# Loongson_Drivers.net
KiCad netlist of a schematic drawn in EasyEDA Pro
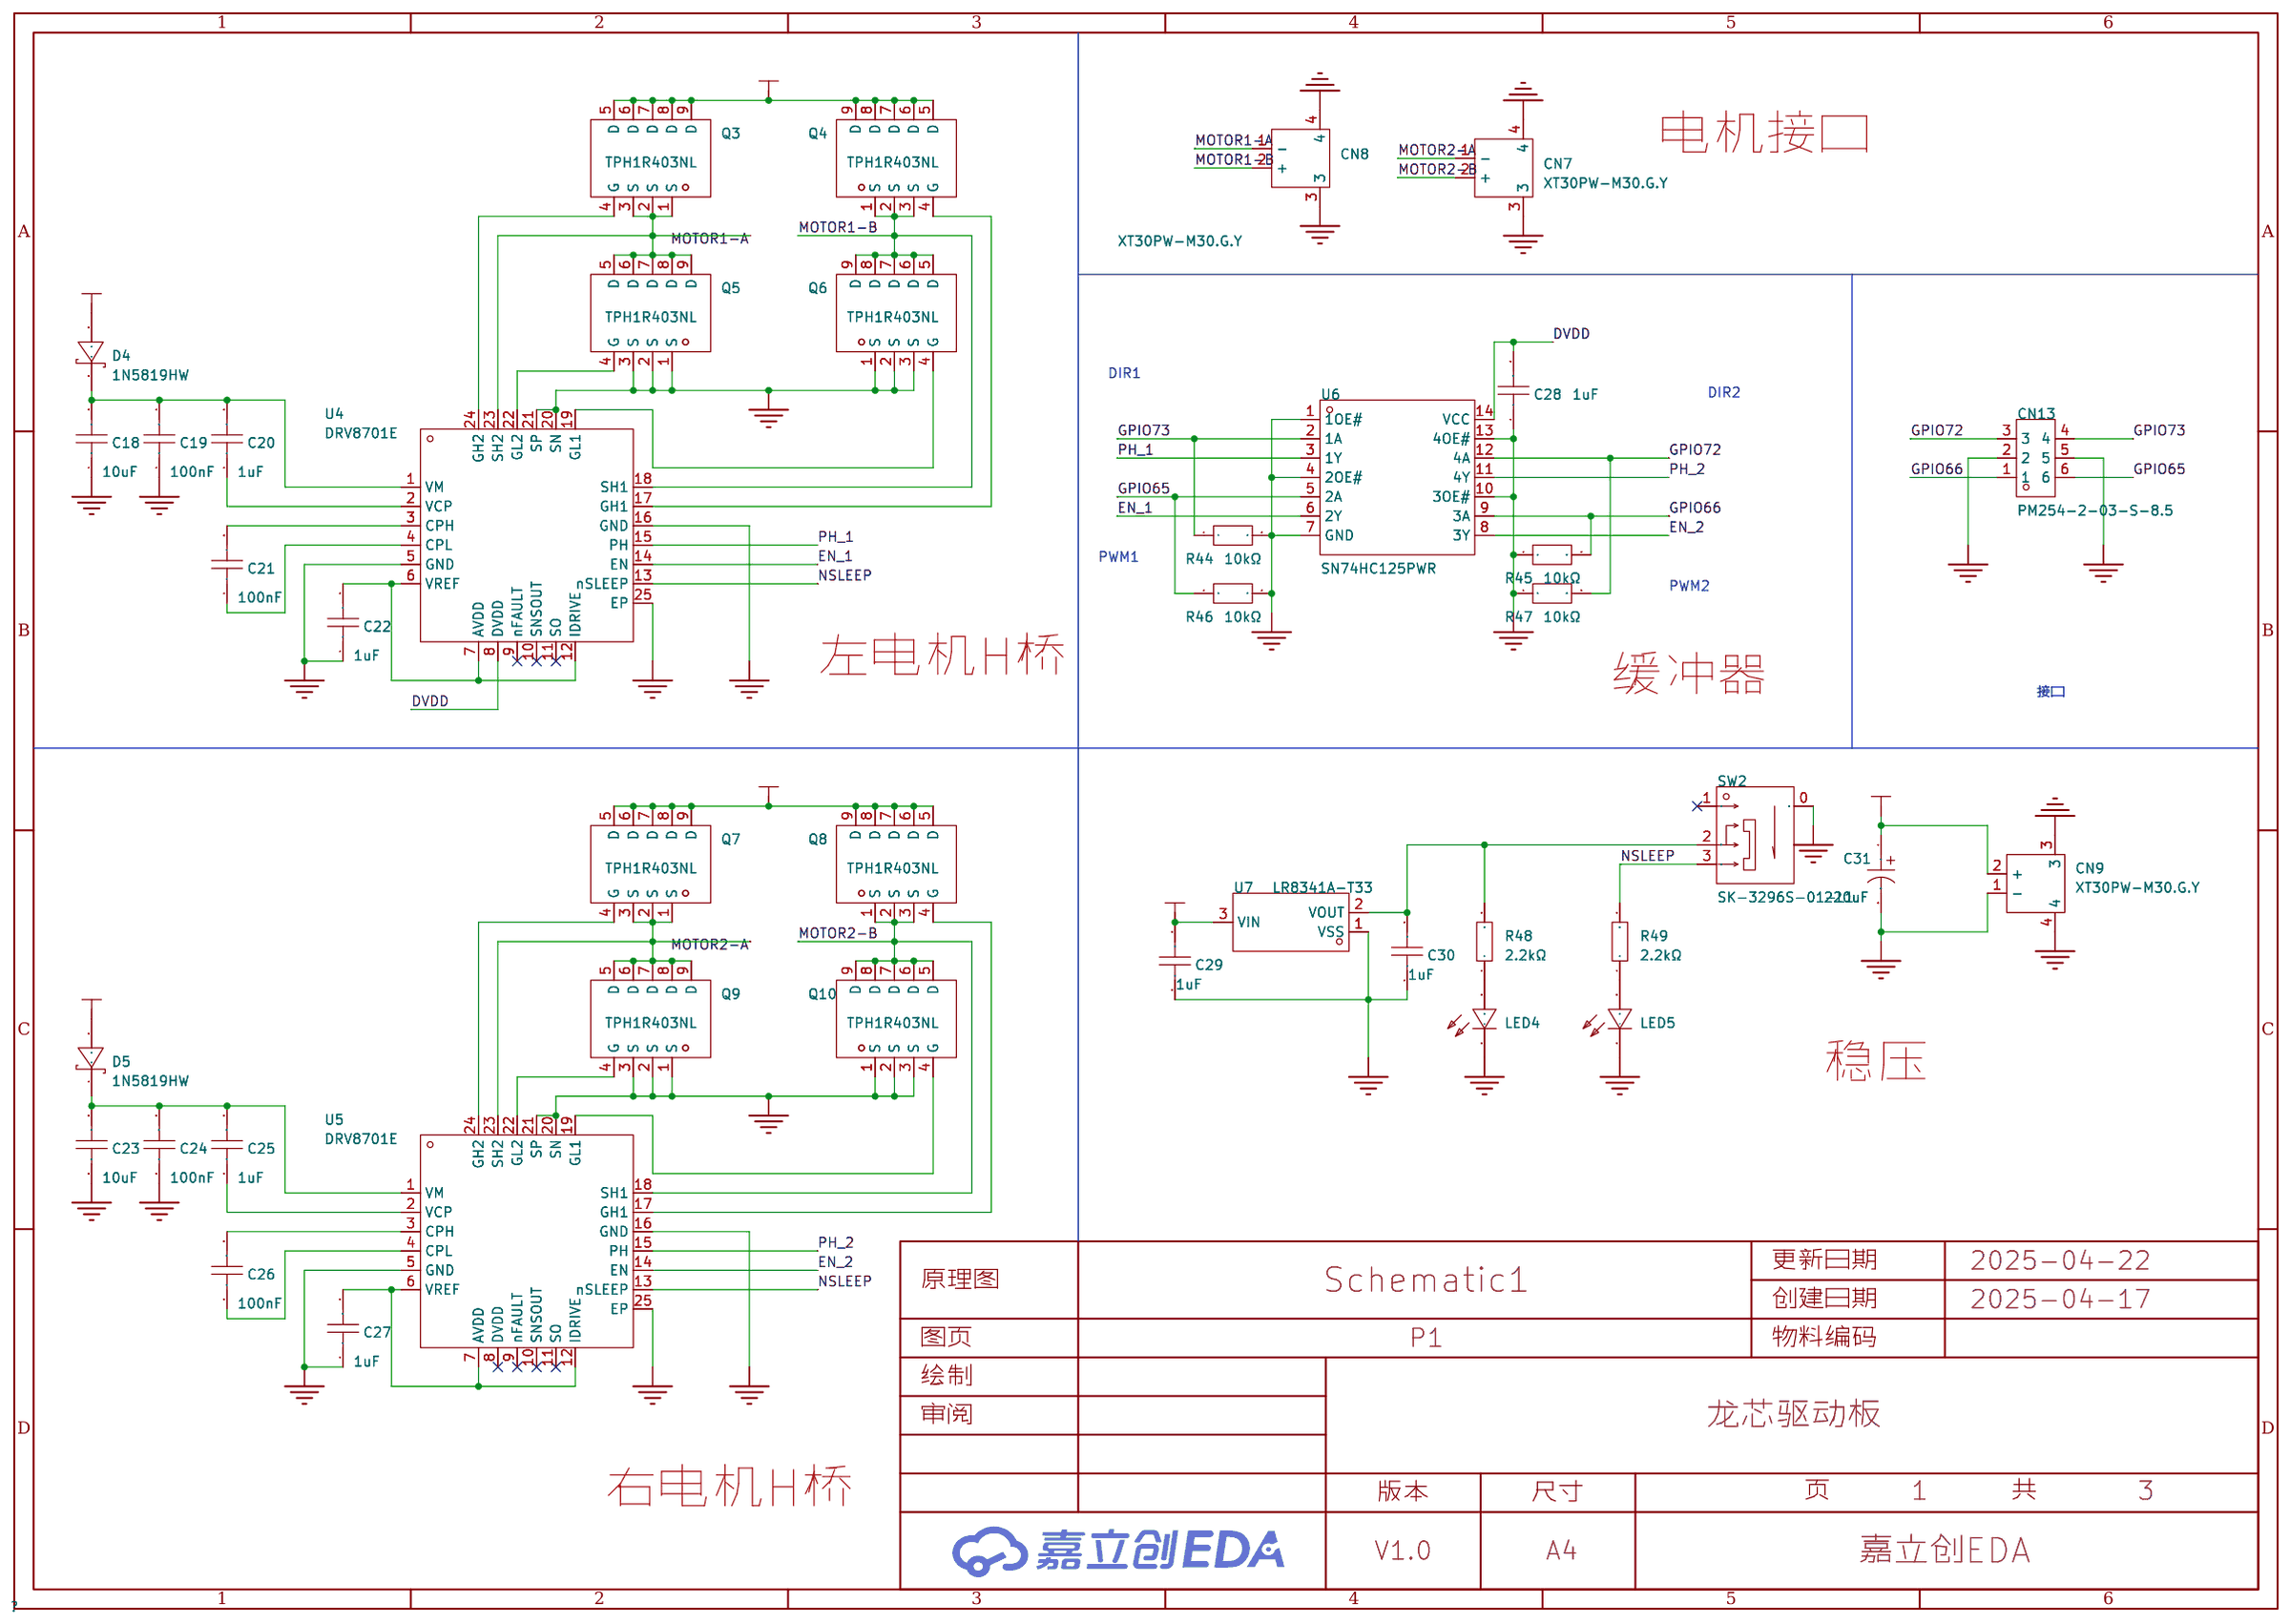
[diagram p0: P1]
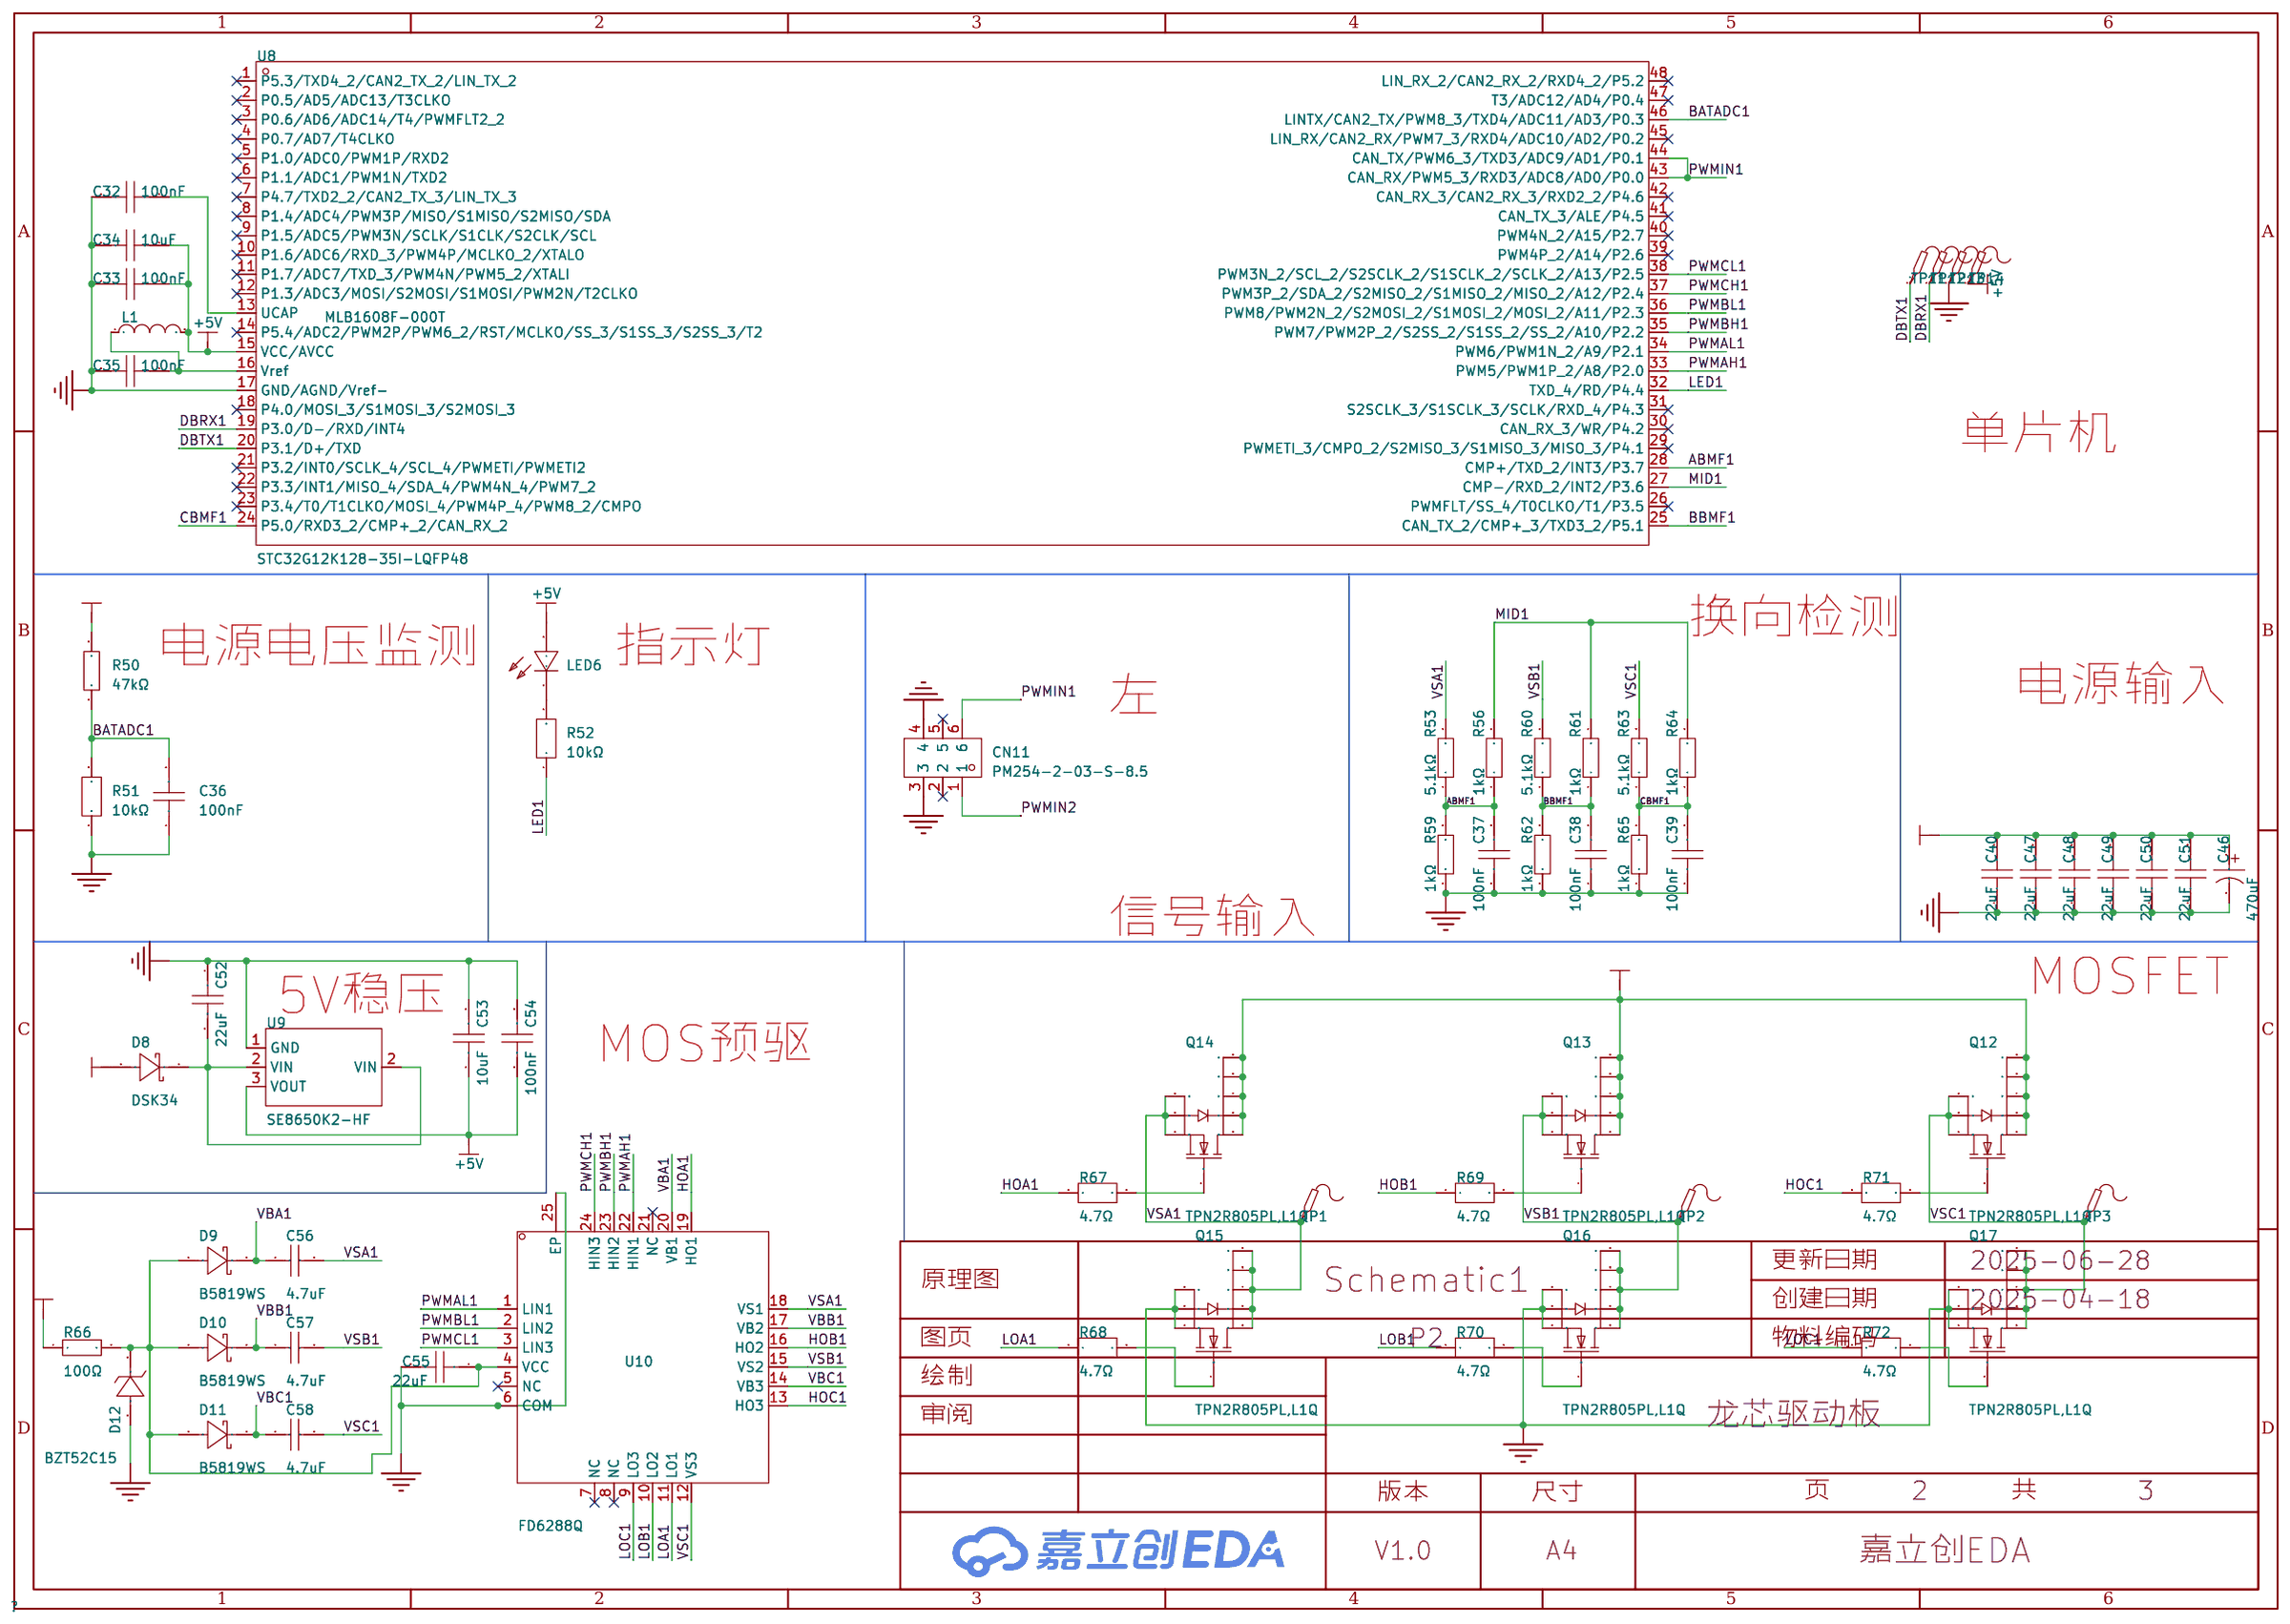
[diagram p1: P2]
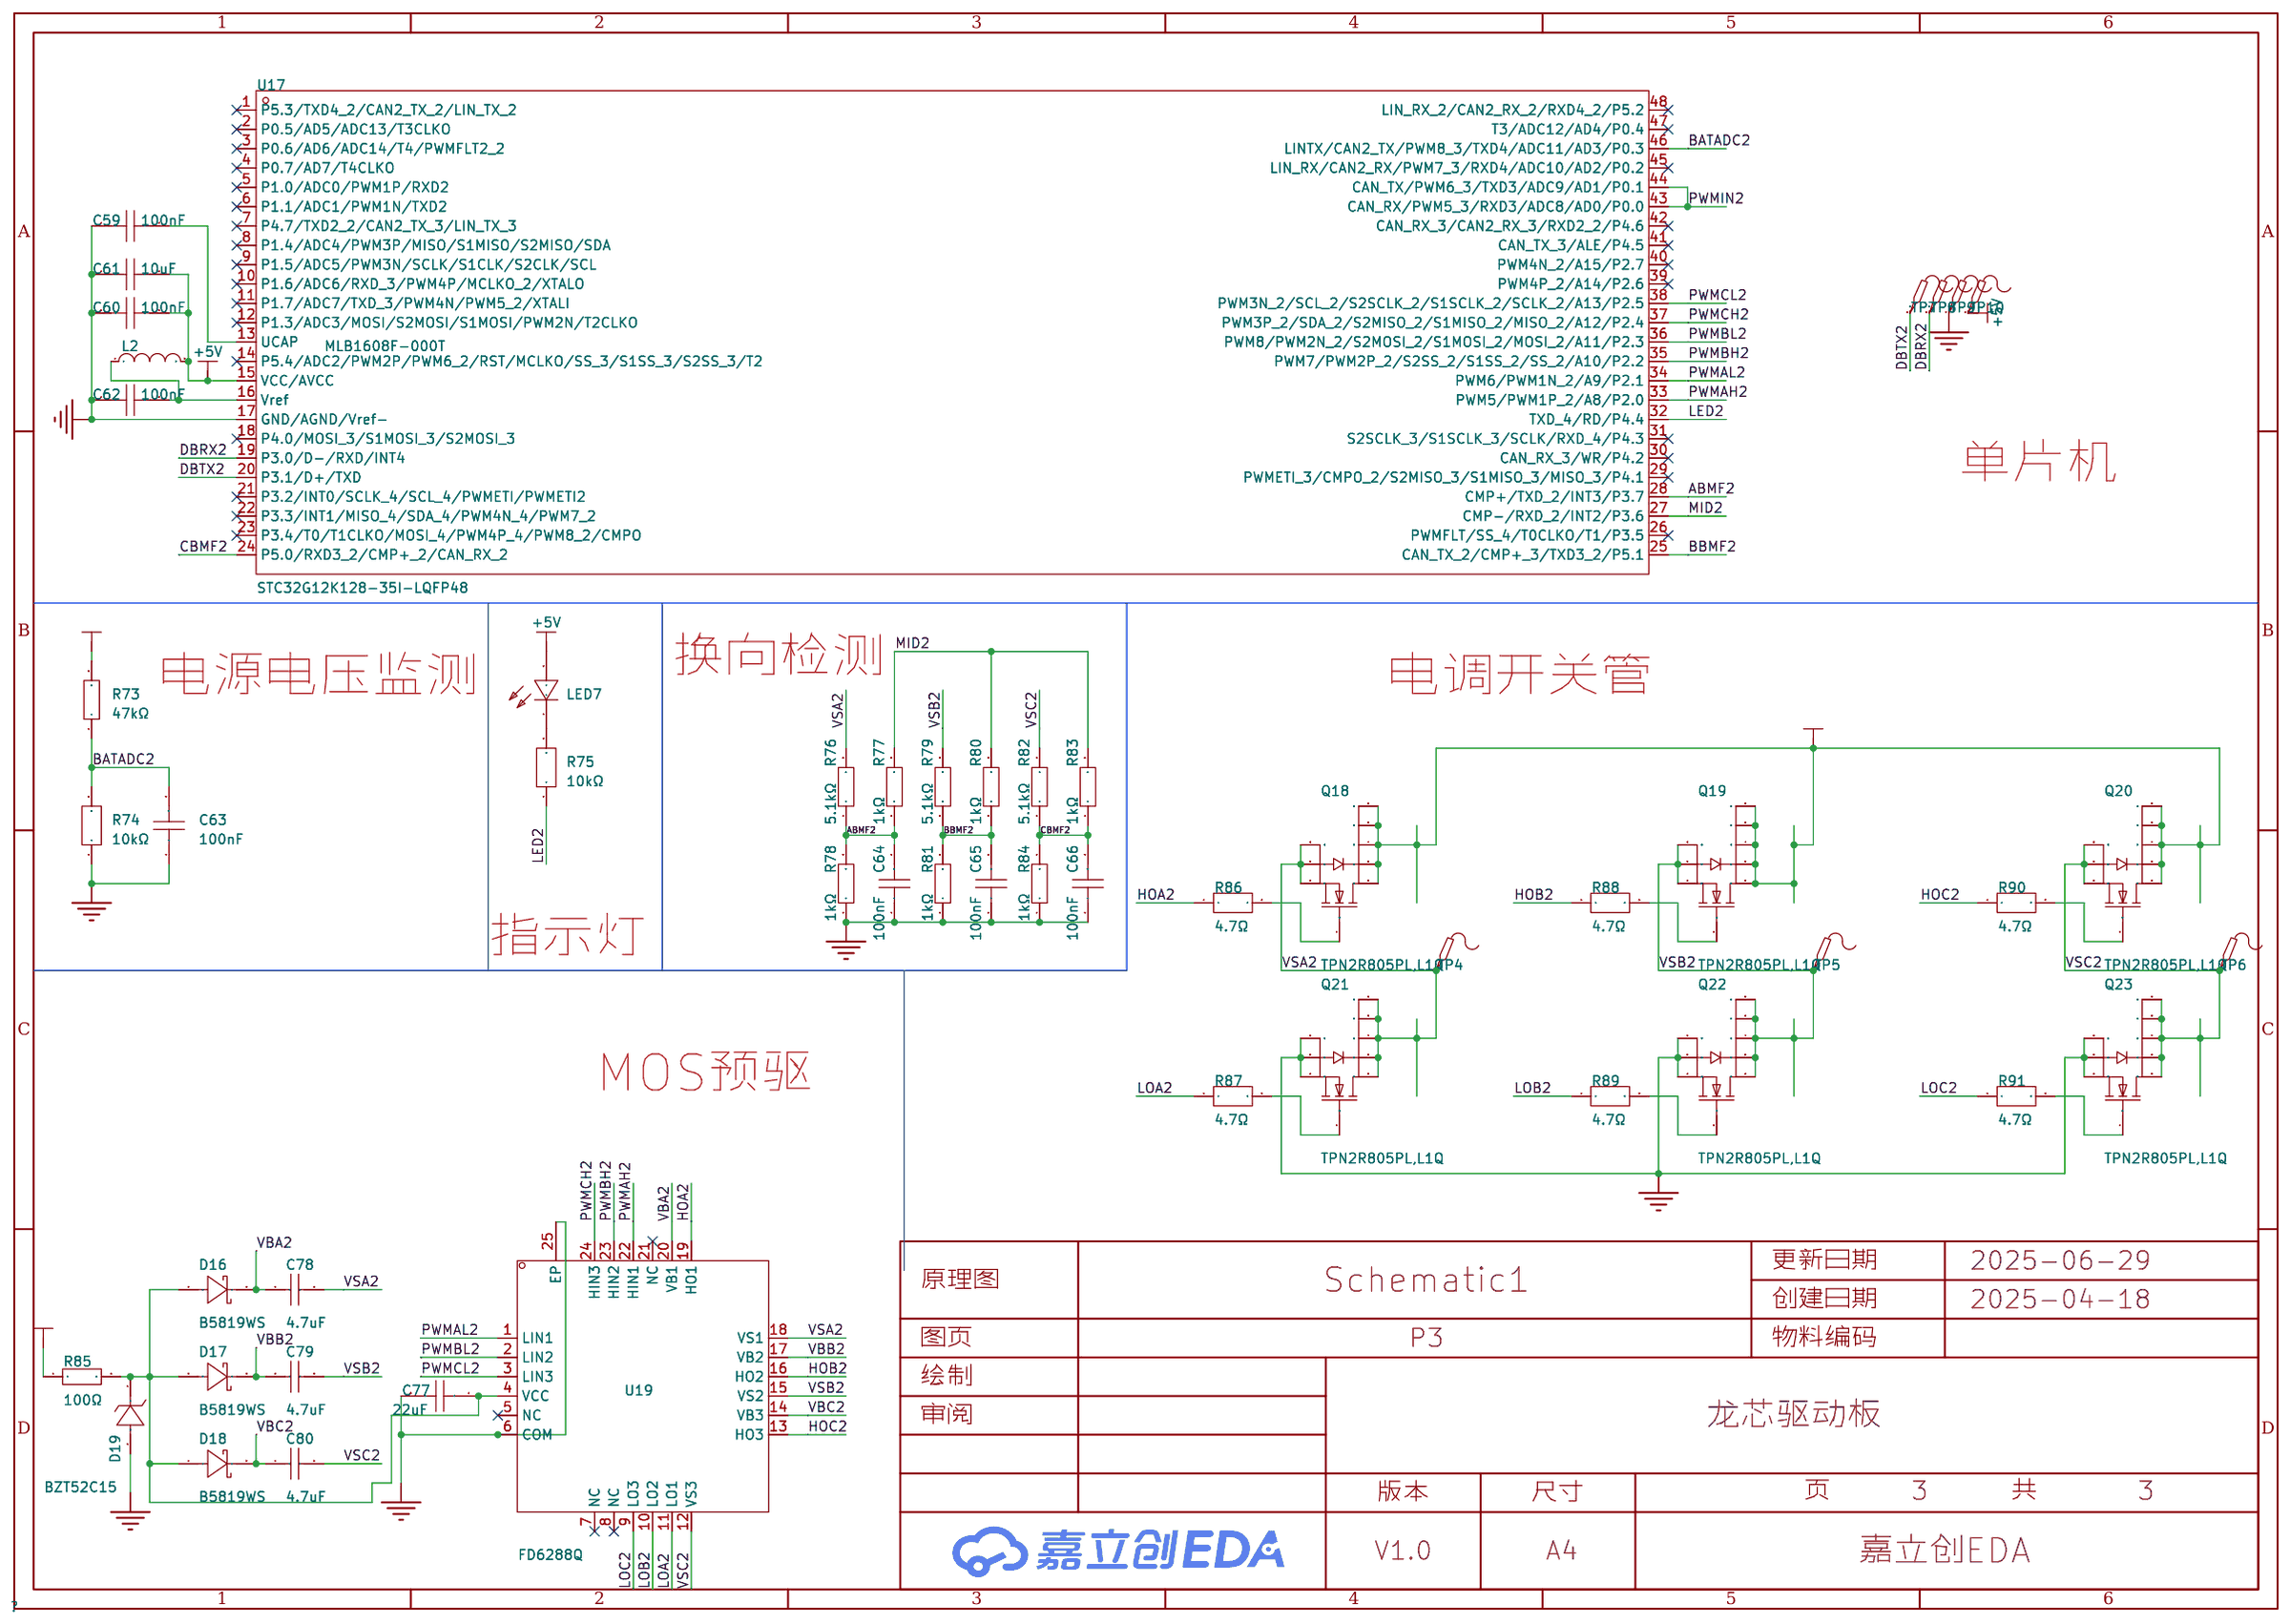
[diagram p2: P3]

(export (version "E")
  (design (tool "Eeschema 10.0.6"))
  (components
    (comp (ref "C18")
      (value "10uF")
      (footprint "easyedapro:C0805")
      (description "容值:10uF;精度:±10%;额定电压:35V;材质(温度系数):X5R;")
      (fields
        (field (name "Manufacturer Part") "CGA0805X5R106K350MT")
        (field (name "Manufacturer") "HRE(芯声)")
      )
      (libsource (lib "easyedapro") (part "CGA0805X5R106K350MT"))
    )
    (comp (ref "C19")
      (value "100nF")
      (footprint "easyedapro:C0603")
      (description "容值:100nF;精度:±10%;额定电压:35V;材质(温度系数):X7R;")
      (fields
        (field (name "Manufacturer Part") "GMK107B7104KAHT")
        (field (name "Manufacturer") "TAIYO YUDEN(太诱)")
      )
      (libsource (lib "easyedapro") (part "GMK107B7104KAHT"))
    )
    (comp (ref "C20")
      (value "1uF")
      (footprint "easyedapro:C0603")
      (description "容值:1uF;精度:±10%;额定电压:50V;材质(温度系数):X5R;")
      (fields
        (field (name "Manufacturer Part") "CL10A105KB8NNNC")
        (field (name "Manufacturer") "SAMSUNG(三星)")
      )
      (libsource (lib "easyedapro") (part "CL10A105KB8NNNC"))
    )
    (comp (ref "C21")
      (value "100nF")
      (footprint "easyedapro:C0603")
      (description "容值:100nF;精度:±10%;额定电压:35V;材质(温度系数):X7R;")
      (fields
        (field (name "Manufacturer Part") "GMK107B7104KAHT")
        (field (name "Manufacturer") "TAIYO YUDEN(太诱)")
      )
      (libsource (lib "easyedapro") (part "GMK107B7104KAHT"))
    )
    (comp (ref "C22")
      (value "1uF")
      (footprint "easyedapro:C0603")
      (description "容值:1uF;精度:±10%;额定电压:50V;材质(温度系数):X5R;")
      (fields
        (field (name "Manufacturer Part") "CL10A105KB8NNNC")
        (field (name "Manufacturer") "SAMSUNG(三星)")
      )
      (libsource (lib "easyedapro") (part "CL10A105KB8NNNC"))
    )
    (comp (ref "C23")
      (value "10uF")
      (footprint "easyedapro:C0805")
      (description "容值:10uF;精度:±10%;额定电压:35V;材质(温度系数):X5R;")
      (fields
        (field (name "Manufacturer Part") "CGA0805X5R106K350MT")
        (field (name "Manufacturer") "HRE(芯声)")
      )
      (libsource (lib "easyedapro") (part "CGA0805X5R106K350MT"))
    )
    (comp (ref "C24")
      (value "100nF")
      (footprint "easyedapro:C0603")
      (description "容值:100nF;精度:±10%;额定电压:35V;材质(温度系数):X7R;")
      (fields
        (field (name "Manufacturer Part") "GMK107B7104KAHT")
        (field (name "Manufacturer") "TAIYO YUDEN(太诱)")
      )
      (libsource (lib "easyedapro") (part "GMK107B7104KAHT"))
    )
    (comp (ref "C25")
      (value "1uF")
      (footprint "easyedapro:C0603")
      (description "容值:1uF;精度:±10%;额定电压:50V;材质(温度系数):X5R;")
      (fields
        (field (name "Manufacturer Part") "CL10A105KB8NNNC")
        (field (name "Manufacturer") "SAMSUNG(三星)")
      )
      (libsource (lib "easyedapro") (part "CL10A105KB8NNNC"))
    )
    (comp (ref "C26")
      (value "100nF")
      (footprint "easyedapro:C0603")
      (description "容值:100nF;精度:±10%;额定电压:35V;材质(温度系数):X7R;")
      (fields
        (field (name "Manufacturer Part") "GMK107B7104KAHT")
        (field (name "Manufacturer") "TAIYO YUDEN(太诱)")
      )
      (libsource (lib "easyedapro") (part "GMK107B7104KAHT"))
    )
    (comp (ref "C27")
      (value "1uF")
      (footprint "easyedapro:C0603")
      (description "容值:1uF;精度:±10%;额定电压:50V;材质(温度系数):X5R;")
      (fields
        (field (name "Manufacturer Part") "CL10A105KB8NNNC")
        (field (name "Manufacturer") "SAMSUNG(三星)")
      )
      (libsource (lib "easyedapro") (part "CL10A105KB8NNNC"))
    )
    (comp (ref "C28")
      (value "1uF")
      (footprint "easyedapro:C0603")
      (description "容值:1uF;精度:±10%;额定电压:50V;材质(温度系数):X5R;")
      (fields
        (field (name "Manufacturer Part") "CL10A105KB8NNNC")
        (field (name "Manufacturer") "SAMSUNG(三星)")
      )
      (libsource (lib "easyedapro") (part "CL10A105KB8NNNC"))
    )
    (comp (ref "C29")
      (value "1uF")
      (footprint "easyedapro:C0603")
      (description "容值:1uF;精度:±10%;额定电压:50V;材质(温度系数):X5R;")
      (fields
        (field (name "Manufacturer Part") "CL10A105KB8NNNC")
        (field (name "Manufacturer") "SAMSUNG(三星)")
      )
      (libsource (lib "easyedapro") (part "CL10A105KB8NNNC"))
    )
    (comp (ref "C30")
      (value "1uF")
      (footprint "easyedapro:C0603")
      (description "容值:1uF;精度:±10%;额定电压:50V;材质(温度系数):X5R;")
      (fields
        (field (name "Manufacturer Part") "CL10A105KB8NNNC")
        (field (name "Manufacturer") "SAMSUNG(三星)")
      )
      (libsource (lib "easyedapro") (part "CL10A105KB8NNNC"))
    )
    (comp (ref "C31")
      (value "220uF")
      (footprint "easyedapro:CAP-SMD_BD8.0-L8.3-W8.3-LS9.1-FD")
      (description "容值:220uF;精度:±20%;额定电压:35V;")
      (fields (field (name "Manufacturer Part") "HV1V227M0810PZ") (field (name "Manufacturer") "HONOR(荣誉)"))
      (libsource (lib "easyedapro") (part "HV1V227M0810PZ"))
    )
    (comp (ref "CN7")
      (value "XT30PW-M30.G.Y")
      (footprint "easyedapro:CONN-TH_XT30PW-M")
      (description "类别:-;类型1:-;")
      (fields (field (name "Manufacturer") "AMASS(艾迈斯)"))
      (libsource (lib "easyedapro") (part "XT30PW-M"))
    )
    (comp (ref "CN8")
      (value "XT30PW-M30.G.Y")
      (footprint "easyedapro:CONN-TH_XT30PW-M")
      (description "类别:-;类型1:-;")
      (fields (field (name "Manufacturer") "AMASS(艾迈斯)"))
      (libsource (lib "easyedapro") (part "XT30PW-M"))
    )
    (comp (ref "CN9")
      (value "XT30PW-M30.G.Y")
      (footprint "easyedapro:CONN-TH_XT30PW-M")
      (description "类别:-;类型1:-;")
      (fields (field (name "Manufacturer") "AMASS(艾迈斯)"))
      (libsource (lib "easyedapro") (part "XT30PW-M"))
    )
    (comp (ref "CN13")
      (value "PM254-2-03-S-8.5")
      (footprint "easyedapro:HDR-SMD_6P-P2.54-V-F-R2-C3-LS7.0")
      (fields (field (name "Manufacturer") "HCTL(华灿天禄)"))
      (libsource (lib "easyedapro") (part "PM254-2-03-S-8.5"))
    )
    (comp (ref "D4")
      (value "1N5819HW")
      (footprint "easyedapro:SOD-123_L2.7-W1.6-LS3.7-RD")
      (description "正向压降(Vf):450mV@1A;直流反向耐压(Vr):40V;整流电流:1A;")
      (fields (field (name "Manufacturer") "DIODES(美台)"))
      (libsource (lib "easyedapro") (part "1N5819HW-7-F"))
    )
    (comp (ref "D5")
      (value "1N5819HW")
      (footprint "easyedapro:SOD-123_L2.7-W1.6-LS3.7-RD")
      (description "正向压降(Vf):450mV@1A;直流反向耐压(Vr):40V;整流电流:1A;")
      (fields (field (name "Manufacturer") "DIODES(美台)"))
      (libsource (lib "easyedapro") (part "1N5819HW-7-F"))
    )
    (comp (ref "LED4")
      (value "NCD0603R1")
      (footprint "easyedapro:LED0603-RD_RED")
      (fields (field (name "Manufacturer") "国星光电"))
      (libsource (lib "easyedapro") (part "FC-DA1608HRK-620D"))
    )
    (comp (ref "LED5")
      (value "NCD0603B1")
      (footprint "easyedapro:LED0603-RD")
      (fields (field (name "Manufacturer") "国星光电"))
      (libsource (lib "easyedapro") (part "FC-DA1608BK-470H10"))
    )
    (comp (ref "Q3")
      (value "TPH1R403NL")
      (footprint "easyedapro:DSOP-8_L5.0-W5.0-P1.27-LS6.0-BL-EP")
      (fields (field (name "Manufacturer") "TOSHIBA(东芝)"))
      (libsource (lib "easyedapro") (part "TPH1R403NL"))
    )
    (comp (ref "Q4")
      (value "TPH1R403NL")
      (footprint "easyedapro:DSOP-8_L5.0-W5.0-P1.27-LS6.0-BL-EP")
      (fields (field (name "Manufacturer") "TOSHIBA(东芝)"))
      (libsource (lib "easyedapro") (part "TPH1R403NL"))
    )
    (comp (ref "Q5")
      (value "TPH1R403NL")
      (footprint "easyedapro:DSOP-8_L5.0-W5.0-P1.27-LS6.0-BL-EP")
      (fields (field (name "Manufacturer") "TOSHIBA(东芝)"))
      (libsource (lib "easyedapro") (part "TPH1R403NL"))
    )
    (comp (ref "Q6")
      (value "TPH1R403NL")
      (footprint "easyedapro:DSOP-8_L5.0-W5.0-P1.27-LS6.0-BL-EP")
      (fields (field (name "Manufacturer") "TOSHIBA(东芝)"))
      (libsource (lib "easyedapro") (part "TPH1R403NL"))
    )
    (comp (ref "Q7")
      (value "TPH1R403NL")
      (footprint "easyedapro:DSOP-8_L5.0-W5.0-P1.27-LS6.0-BL-EP")
      (fields (field (name "Manufacturer") "TOSHIBA(东芝)"))
      (libsource (lib "easyedapro") (part "TPH1R403NL"))
    )
    (comp (ref "Q8")
      (value "TPH1R403NL")
      (footprint "easyedapro:DSOP-8_L5.0-W5.0-P1.27-LS6.0-BL-EP")
      (fields (field (name "Manufacturer") "TOSHIBA(东芝)"))
      (libsource (lib "easyedapro") (part "TPH1R403NL"))
    )
    (comp (ref "Q9")
      (value "TPH1R403NL")
      (footprint "easyedapro:DSOP-8_L5.0-W5.0-P1.27-LS6.0-BL-EP")
      (fields (field (name "Manufacturer") "TOSHIBA(东芝)"))
      (libsource (lib "easyedapro") (part "TPH1R403NL"))
    )
    (comp (ref "Q10")
      (value "TPH1R403NL")
      (footprint "easyedapro:DSOP-8_L5.0-W5.0-P1.27-LS6.0-BL-EP")
      (fields (field (name "Manufacturer") "TOSHIBA(东芝)"))
      (libsource (lib "easyedapro") (part "TPH1R403NL"))
    )
    (comp (ref "R44")
      (value "10kΩ")
      (footprint "easyedapro:R0603")
      (description "电阻类型:厚膜电阻;阻值:10kΩ;精度:±5%;功率:100mW;最大工作电压:75V;温度系数:±100ppm/°C;")
      (fields (field (name "Manufacturer Part") "FRC0603J103TS") (field (name "Manufacturer") "FOJAN(富捷)"))
      (libsource (lib "easyedapro") (part "FRC0603J103TS"))
    )
    (comp (ref "R45")
      (value "10kΩ")
      (footprint "easyedapro:R0603")
      (description "电阻类型:厚膜电阻;阻值:10kΩ;精度:±5%;功率:100mW;最大工作电压:75V;温度系数:±100ppm/°C;")
      (fields (field (name "Manufacturer Part") "FRC0603J103TS") (field (name "Manufacturer") "FOJAN(富捷)"))
      (libsource (lib "easyedapro") (part "FRC0603J103TS"))
    )
    (comp (ref "R46")
      (value "10kΩ")
      (footprint "easyedapro:R0603")
      (description "电阻类型:厚膜电阻;阻值:10kΩ;精度:±5%;功率:100mW;最大工作电压:75V;温度系数:±100ppm/°C;")
      (fields (field (name "Manufacturer Part") "FRC0603J103TS") (field (name "Manufacturer") "FOJAN(富捷)"))
      (libsource (lib "easyedapro") (part "FRC0603J103TS"))
    )
    (comp (ref "R47")
      (value "10kΩ")
      (footprint "easyedapro:R0603")
      (description "电阻类型:厚膜电阻;阻值:10kΩ;精度:±5%;功率:100mW;最大工作电压:75V;温度系数:±100ppm/°C;")
      (fields (field (name "Manufacturer Part") "FRC0603J103TS") (field (name "Manufacturer") "FOJAN(富捷)"))
      (libsource (lib "easyedapro") (part "FRC0603J103TS"))
    )
    (comp (ref "R48")
      (value "2.2kΩ")
      (footprint "easyedapro:R0603")
      (description "电阻类型:厚膜电阻;阻值:2.2kΩ;精度:±1%;功率:100mW;最大工作电压:75V;温度系数:±100ppm/°C;")
      (fields
        (field (name "Manufacturer Part") "0603WAF2201T5E")
        (field (name "Manufacturer") "UNI-ROYAL(厚声)")
      )
      (libsource (lib "easyedapro") (part "0603WAF2201T5E"))
    )
    (comp (ref "R49")
      (value "2.2kΩ")
      (footprint "easyedapro:R0603")
      (description "电阻类型:厚膜电阻;阻值:2.2kΩ;精度:±1%;功率:100mW;最大工作电压:75V;温度系数:±100ppm/°C;")
      (fields
        (field (name "Manufacturer Part") "0603WAF2201T5E")
        (field (name "Manufacturer") "UNI-ROYAL(厚声)")
      )
      (libsource (lib "easyedapro") (part "0603WAF2201T5E"))
    )
    (comp (ref "SW2")
      (value "SK-3296S-01-L1")
      (footprint "easyedapro:SW-SMD_3P-P1.50_L2.7-W6.6")
      (description "电路结构:单刀双掷;安装方式:卧贴;开关颜色:黑色;额定电流(DC):50mA;额定电压(DC):12V;额定电流(AC):50mA;额定电压(AC):12V;机械寿命:1万次;")
      (fields (field (name "Manufacturer") "XKB Connectivity(中国星坤)"))
      (libsource (lib "easyedapro") (part "SK-3296S-01-L1"))
    )
    (comp (ref "U4")
      (value "DRV8701E")
      (footprint "easyedapro:VQFN-24_L4.0-W4.0-P0.50-BL-EP2.5")
      (description "DRV8701 47V H 桥智能栅极驱动器")
      (fields (field (name "Manufacturer") "TI(德州仪器)"))
      (libsource (lib "easyedapro") (part "DRV8701ERGET"))
    )
    (comp (ref "U5")
      (value "DRV8701E")
      (footprint "easyedapro:VQFN-24_L4.0-W4.0-P0.50-BL-EP2.5")
      (description "DRV8701 47V H 桥智能栅极驱动器")
      (fields (field (name "Manufacturer") "TI(德州仪器)"))
      (libsource (lib "easyedapro") (part "DRV8701ERGET"))
    )
    (comp (ref "U6")
      (value "SN74HC125PWR")
      (footprint "easyedapro:TSSOP-14_L5.0-W4.4-P0.65-LS6.5-BL")
      (description "输入类型:-;电源电压:2V~6V;元件数:4;每个元件位数:1;灌电流(IOL):7.8mA;拉电流(IOH):7.8mA;")
      (fields (field (name "Manufacturer") "TI(德州仪器)"))
      (libsource (lib "easyedapro") (part "SN74HC125PWR"))
    )
    (comp (ref "U7")
      (value "LR8341A-T33")
      (footprint "easyedapro:SOT-23-3L_L2.9-W1.6-P1.90-LS2.8-BL")
      (description "输出类型:固定;最大输入电压:40V;输出电压:3.3V;最大输出电流:100mA;电源纹波抑制比(PSRR):55dB@(1kHz);输出极性:正极;")
      (fields (field (name "Manufacturer") "LR(朗瑞)"))
      (libsource (lib "easyedapro") (part "LR8341A-T33"))
    )
    (comp (ref "C32")
      (value "100nF")
      (footprint "easyedapro:C0603")
      (description "容值:100nF;精度:±10%;额定电压:50V;材质(温度系数):X7R;")
      (fields
        (field (name "Manufacturer Part") "CGA0603X7R104K500JT")
        (field (name "Manufacturer") "HRE(芯声)")
      )
      (libsource (lib "easyedapro") (part "CGA0603X7R104K500JT"))
    )
    (comp (ref "C33")
      (value "100nF")
      (footprint "easyedapro:C0603")
      (description "容值:100nF;精度:±10%;额定电压:50V;材质(温度系数):X7R;")
      (fields
        (field (name "Manufacturer Part") "CGA0603X7R104K500JT")
        (field (name "Manufacturer") "HRE(芯声)")
      )
      (libsource (lib "easyedapro") (part "CGA0603X7R104K500JT"))
    )
    (comp (ref "C34")
      (value "10uF")
      (footprint "easyedapro:C0603")
      (description "容值:10uF;精度:±10%;额定电压:10V;温度系数:X5R;")
      (fields
        (field (name "Manufacturer Part") "CGA0603X5R106K100JT")
        (field (name "Manufacturer") "HRE(芯声)")
      )
      (libsource (lib "easyedapro") (part "CGA0603X5R106K100JT"))
    )
    (comp (ref "C35")
      (value "100nF")
      (footprint "easyedapro:C0603")
      (description "容值:100nF;精度:±10%;额定电压:50V;材质(温度系数):X7R;")
      (fields
        (field (name "Manufacturer Part") "CGA0603X7R104K500JT")
        (field (name "Manufacturer") "HRE(芯声)")
      )
      (libsource (lib "easyedapro") (part "CGA0603X7R104K500JT"))
    )
    (comp (ref "C36")
      (value "100nF")
      (footprint "easyedapro:C0603")
      (description "容值:100nF;精度:±10%;额定电压:50V;材质(温度系数):X7R;")
      (fields
        (field (name "Manufacturer Part") "CGA0603X7R104K500JT")
        (field (name "Manufacturer") "HRE(芯声)")
      )
      (libsource (lib "easyedapro") (part "CGA0603X7R104K500JT"))
    )
    (comp (ref "C37")
      (value "100nF")
      (footprint "easyedapro:C0603")
      (description "容值:100nF;精度:±10%;额定电压:50V;材质(温度系数):X7R;")
      (fields
        (field (name "Manufacturer Part") "CGA0603X7R104K500JT")
        (field (name "Manufacturer") "HRE(芯声)")
      )
      (libsource (lib "easyedapro") (part "CGA0603X7R104K500JT"))
    )
    (comp (ref "C38")
      (value "100nF")
      (footprint "easyedapro:C0603")
      (description "容值:100nF;精度:±10%;额定电压:50V;材质(温度系数):X7R;")
      (fields
        (field (name "Manufacturer Part") "CGA0603X7R104K500JT")
        (field (name "Manufacturer") "HRE(芯声)")
      )
      (libsource (lib "easyedapro") (part "CGA0603X7R104K500JT"))
    )
    (comp (ref "C39")
      (value "100nF")
      (footprint "easyedapro:C0603")
      (description "容值:100nF;精度:±10%;额定电压:50V;材质(温度系数):X7R;")
      (fields
        (field (name "Manufacturer Part") "CGA0603X7R104K500JT")
        (field (name "Manufacturer") "HRE(芯声)")
      )
      (libsource (lib "easyedapro") (part "CGA0603X7R104K500JT"))
    )
    (comp (ref "C40")
      (value "22uF")
      (footprint "easyedapro:C0805")
      (description "容值:22uF;精度:±20%;额定电压:25V;温度系数:X5R;")
      (fields
        (field (name "Manufacturer Part") "CGA0805X5R226M250MT")
        (field (name "Manufacturer") "HRE(芯声)")
      )
      (libsource (lib "easyedapro") (part "CGA0805X5R226M250MT"))
    )
    (comp (ref "C46")
      (value "470uF")
      (footprint "easyedapro:CAP-SMD_BD10.0-L10.3-W10.3-LS11.0-R-RD")
      (description "容值:470uF;精度:±20%;额定电压:35V;纹波电流:286mA@120Hz;等效串联电阻(ESR):-;")
      (fields (field (name "Manufacturer Part") "RVT1V471M1010") (field (name "Manufacturer") "ROQANG(容强)"))
      (libsource (lib "easyedapro") (part "RVT1V471M1010-C72519"))
    )
    (comp (ref "C47")
      (value "22uF")
      (footprint "easyedapro:C0805")
      (description "容值:22uF;精度:±20%;额定电压:25V;温度系数:X5R;")
      (fields
        (field (name "Manufacturer Part") "CGA0805X5R226M250MT")
        (field (name "Manufacturer") "HRE(芯声)")
      )
      (libsource (lib "easyedapro") (part "CGA0805X5R226M250MT"))
    )
    (comp (ref "C48")
      (value "22uF")
      (footprint "easyedapro:C0805")
      (description "容值:22uF;精度:±20%;额定电压:25V;温度系数:X5R;")
      (fields
        (field (name "Manufacturer Part") "CGA0805X5R226M250MT")
        (field (name "Manufacturer") "HRE(芯声)")
      )
      (libsource (lib "easyedapro") (part "CGA0805X5R226M250MT"))
    )
    (comp (ref "C49")
      (value "22uF")
      (footprint "easyedapro:C0805")
      (description "容值:22uF;精度:±20%;额定电压:25V;温度系数:X5R;")
      (fields
        (field (name "Manufacturer Part") "CGA0805X5R226M250MT")
        (field (name "Manufacturer") "HRE(芯声)")
      )
      (libsource (lib "easyedapro") (part "CGA0805X5R226M250MT"))
    )
    (comp (ref "C50")
      (value "22uF")
      (footprint "easyedapro:C0805")
      (description "容值:22uF;精度:±20%;额定电压:25V;温度系数:X5R;")
      (fields
        (field (name "Manufacturer Part") "CGA0805X5R226M250MT")
        (field (name "Manufacturer") "HRE(芯声)")
      )
      (libsource (lib "easyedapro") (part "CGA0805X5R226M250MT"))
    )
    (comp (ref "C51")
      (value "22uF")
      (footprint "easyedapro:C0805")
      (description "容值:22uF;精度:±20%;额定电压:25V;温度系数:X5R;")
      (fields
        (field (name "Manufacturer Part") "CGA0805X5R226M250MT")
        (field (name "Manufacturer") "HRE(芯声)")
      )
      (libsource (lib "easyedapro") (part "CGA0805X5R226M250MT"))
    )
    (comp (ref "C52")
      (value "22uF")
      (footprint "easyedapro:C0805")
      (description "容值:22uF;精度:±20%;额定电压:25V;温度系数:X5R;")
      (fields
        (field (name "Manufacturer Part") "CGA0805X5R226M250MT")
        (field (name "Manufacturer") "HRE(芯声)")
      )
      (libsource (lib "easyedapro") (part "CGA0805X5R226M250MT"))
    )
    (comp (ref "C53")
      (value "10uF")
      (footprint "easyedapro:C0603")
      (description "容值:10uF;精度:±10%;额定电压:10V;温度系数:X5R;")
      (fields
        (field (name "Manufacturer Part") "CGA0603X5R106K100JT")
        (field (name "Manufacturer") "HRE(芯声)")
      )
      (libsource (lib "easyedapro") (part "CGA0603X5R106K100JT"))
    )
    (comp (ref "C54")
      (value "100nF")
      (footprint "easyedapro:C0603")
      (description "容值:100nF;精度:±10%;额定电压:50V;材质(温度系数):X7R;")
      (fields
        (field (name "Manufacturer Part") "CGA0603X7R104K500JT")
        (field (name "Manufacturer") "HRE(芯声)")
      )
      (libsource (lib "easyedapro") (part "CGA0603X7R104K500JT"))
    )
    (comp (ref "C55")
      (value "22uF")
      (footprint "easyedapro:C0805")
      (description "容值:22uF;精度:±20%;额定电压:25V;温度系数:X5R;")
      (fields
        (field (name "Manufacturer Part") "CGA0805X5R226M250MT")
        (field (name "Manufacturer") "HRE(芯声)")
      )
      (libsource (lib "easyedapro") (part "CGA0805X5R226M250MT"))
    )
    (comp (ref "C56")
      (value "4.7uF")
      (footprint "easyedapro:C0805")
      (description "容值:4.7uF;精度:±10%;额定电压:25V;材质(温度系数):X5R;")
      (fields
        (field (name "Manufacturer Part") "CL21A475KAQNNNE")
        (field (name "Manufacturer") "SAMSUNG(三星)")
      )
      (libsource (lib "easyedapro") (part "CL21A475KAQNNNE"))
    )
    (comp (ref "C57")
      (value "4.7uF")
      (footprint "easyedapro:C0805")
      (description "容值:4.7uF;精度:±10%;额定电压:25V;材质(温度系数):X5R;")
      (fields
        (field (name "Manufacturer Part") "CL21A475KAQNNNE")
        (field (name "Manufacturer") "SAMSUNG(三星)")
      )
      (libsource (lib "easyedapro") (part "CL21A475KAQNNNE"))
    )
    (comp (ref "C58")
      (value "4.7uF")
      (footprint "easyedapro:C0805")
      (description "容值:4.7uF;精度:±10%;额定电压:25V;材质(温度系数):X5R;")
      (fields
        (field (name "Manufacturer Part") "CL21A475KAQNNNE")
        (field (name "Manufacturer") "SAMSUNG(三星)")
      )
      (libsource (lib "easyedapro") (part "CL21A475KAQNNNE"))
    )
    (comp (ref "CN11")
      (value "PM254-2-03-S-8.5")
      (footprint "easyedapro:HDR-SMD_6P-P2.54-V-F-R2-C3-LS7.0")
      (fields (field (name "Manufacturer") "HCTL(华灿天禄)"))
      (libsource (lib "easyedapro") (part "PM254-2-03-S-8.5"))
    )
    (comp (ref "D8")
      (value "DSK34")
      (footprint "easyedapro:SOD-123FL_L2.7-W1.8-LS3.8-RD")
      (description "二极管配置:独立式;正向压降(Vf):550mV@3A;直流反向耐压(Vr):40V;整流电流:3A;")
      (fields (field (name "Manufacturer") "宏迦橙"))
      (libsource (lib "easyedapro") (part "DSK34_C7502709"))
    )
    (comp (ref "D9")
      (value "B5819WS")
      (footprint "easyedapro:SOD-323_L1.7-W1.3-LS2.5-FD")
      (description "二极管配置:独立式;正向压降(Vf):600mV@1.0A;直流反向耐压(Vr):40V;整流电流:1A;")
      (fields (field (name "Manufacturer") "宏迦橙"))
      (libsource (lib "easyedapro") (part "B5819WS_C7420331"))
    )
    (comp (ref "D10")
      (value "B5819WS")
      (footprint "easyedapro:SOD-323_L1.7-W1.3-LS2.5-FD")
      (description "二极管配置:独立式;正向压降(Vf):600mV@1.0A;直流反向耐压(Vr):40V;整流电流:1A;")
      (fields (field (name "Manufacturer") "宏迦橙"))
      (libsource (lib "easyedapro") (part "B5819WS_C7420331"))
    )
    (comp (ref "D11")
      (value "B5819WS")
      (footprint "easyedapro:SOD-323_L1.7-W1.3-LS2.5-FD")
      (description "二极管配置:独立式;正向压降(Vf):600mV@1.0A;直流反向耐压(Vr):40V;整流电流:1A;")
      (fields (field (name "Manufacturer") "宏迦橙"))
      (libsource (lib "easyedapro") (part "B5819WS_C7420331"))
    )
    (comp (ref "D12")
      (value "BZT52C15")
      (footprint "easyedapro:SOD-123_L2.7-W1.6-LS3.7-RD")
      (description "二极管配置:独立式;稳压值(标称值):15V;稳压值(范围):14.25V~15.75V;耗散功率(Pd):500mW;")
      (fields (field (name "Manufacturer") "宏嘉诚"))
      (libsource (lib "easyedapro") (part "BZT52C15_C19077412"))
    )
    (comp (ref "L1")
      (value "MLB1608F-000T")
      (footprint "easyedapro:L0603")
      (description "阻抗@频率:0Ω@100MHz;误差:±25%;直流电阻(DCR):-;")
      (fields (field (name "Manufacturer") "MetalLions(美铼)"))
      (libsource (lib "easyedapro") (part "MLB1608F-000T"))
    )
    (comp (ref "LED6")
      (value "NCD0603R1")
      (footprint "easyedapro:LED0603-RD_RED")
      (fields (field (name "Manufacturer") "国星光电"))
      (libsource (lib "easyedapro") (part "FC-DA1608HRK-620D"))
    )
    (comp (ref "Q12")
      (value "TPN2R805PL,L1Q")
      (footprint "easyedapro:TSON-8_L3.1-W3.1-P0.65-LS3.3-BL-EP")
      (fields (field (name "Manufacturer") "TOSHIBA(东芝)"))
      (libsource (lib "easyedapro") (part "TPN2R805PL,L1Q"))
    )
    (comp (ref "Q13")
      (value "TPN2R805PL,L1Q")
      (footprint "easyedapro:TSON-8_L3.1-W3.1-P0.65-LS3.3-BL-EP")
      (fields (field (name "Manufacturer") "TOSHIBA(东芝)"))
      (libsource (lib "easyedapro") (part "TPN2R805PL,L1Q"))
    )
    (comp (ref "Q14")
      (value "TPN2R805PL,L1Q")
      (footprint "easyedapro:TSON-8_L3.1-W3.1-P0.65-LS3.3-BL-EP")
      (fields (field (name "Manufacturer") "TOSHIBA(东芝)"))
      (libsource (lib "easyedapro") (part "TPN2R805PL,L1Q"))
    )
    (comp (ref "Q15")
      (value "TPN2R805PL,L1Q")
      (footprint "easyedapro:TSON-8_L3.1-W3.1-P0.65-LS3.3-BL-EP")
      (fields (field (name "Manufacturer") "TOSHIBA(东芝)"))
      (libsource (lib "easyedapro") (part "TPN2R805PL,L1Q"))
    )
    (comp (ref "Q16")
      (value "TPN2R805PL,L1Q")
      (footprint "easyedapro:TSON-8_L3.1-W3.1-P0.65-LS3.3-BL-EP")
      (fields (field (name "Manufacturer") "TOSHIBA(东芝)"))
      (libsource (lib "easyedapro") (part "TPN2R805PL,L1Q"))
    )
    (comp (ref "Q17")
      (value "TPN2R805PL,L1Q")
      (footprint "easyedapro:TSON-8_L3.1-W3.1-P0.65-LS3.3-BL-EP")
      (fields (field (name "Manufacturer") "TOSHIBA(东芝)"))
      (libsource (lib "easyedapro") (part "TPN2R805PL,L1Q"))
    )
    (comp (ref "R50")
      (value "47kΩ")
      (footprint "easyedapro:R0603")
      (description "电阻类型:厚膜电阻;阻值:47kΩ;精度:±1%;功率:100mW;最大工作电压:75V;温度系数:±100ppm/°C;")
      (fields
        (field (name "Manufacturer Part") "0603WAF4702T5E")
        (field (name "Manufacturer") "UNI-ROYAL(厚声)")
      )
      (libsource (lib "easyedapro") (part "0603WAF4702T5E"))
    )
    (comp (ref "R51")
      (value "10kΩ")
      (footprint "easyedapro:R0603")
      (description "电阻类型:厚膜电阻;阻值:10kΩ;精度:±5%;功率:100mW;最大工作电压:75V;温度系数:±100ppm/°C;")
      (fields (field (name "Manufacturer Part") "FRC0603J103TS") (field (name "Manufacturer") "FOJAN(富捷)"))
      (libsource (lib "easyedapro") (part "FRC0603J103TS"))
    )
    (comp (ref "R52")
      (value "10kΩ")
      (footprint "easyedapro:R0603")
      (description "电阻类型:厚膜电阻;阻值:10kΩ;精度:±5%;功率:100mW;最大工作电压:75V;温度系数:±100ppm/°C;")
      (fields (field (name "Manufacturer Part") "FRC0603J103TS") (field (name "Manufacturer") "FOJAN(富捷)"))
      (libsource (lib "easyedapro") (part "FRC0603J103TS"))
    )
    (comp (ref "R53")
      (value "5.1kΩ")
      (footprint "easyedapro:R0603")
      (description "电阻类型:厚膜电阻;阻值:5.1kΩ;精度:±1%;功率:100mW;最大工作电压:75V;温度系数:±100ppm/°C;")
      (fields
        (field (name "Manufacturer Part") "0603WAF5101T5E")
        (field (name "Manufacturer") "UNI-ROYAL(厚声)")
      )
      (libsource (lib "easyedapro") (part "0603WAF5101T5E"))
    )
    (comp (ref "R56")
      (value "1kΩ")
      (footprint "easyedapro:R0603")
      (description "电阻类型:厚膜电阻;阻值:1kΩ;精度:±1%;功率:100mW;最大工作电压:75V;温度系数:±100ppm/°C;")
      (fields
        (field (name "Manufacturer Part") "0603WAF1001T5E")
        (field (name "Manufacturer") "UNI-ROYAL(厚声)")
      )
      (libsource (lib "easyedapro") (part "0603WAF1001T5E"))
    )
    (comp (ref "R59")
      (value "1kΩ")
      (footprint "easyedapro:R0603")
      (description "电阻类型:厚膜电阻;阻值:1kΩ;精度:±1%;功率:100mW;最大工作电压:75V;温度系数:±100ppm/°C;")
      (fields
        (field (name "Manufacturer Part") "0603WAF1001T5E")
        (field (name "Manufacturer") "UNI-ROYAL(厚声)")
      )
      (libsource (lib "easyedapro") (part "0603WAF1001T5E"))
    )
    (comp (ref "R60")
      (value "5.1kΩ")
      (footprint "easyedapro:R0603")
      (description "电阻类型:厚膜电阻;阻值:5.1kΩ;精度:±1%;功率:100mW;最大工作电压:75V;温度系数:±100ppm/°C;")
      (fields
        (field (name "Manufacturer Part") "0603WAF5101T5E")
        (field (name "Manufacturer") "UNI-ROYAL(厚声)")
      )
      (libsource (lib "easyedapro") (part "0603WAF5101T5E"))
    )
    (comp (ref "R61")
      (value "1kΩ")
      (footprint "easyedapro:R0603")
      (description "电阻类型:厚膜电阻;阻值:1kΩ;精度:±1%;功率:100mW;最大工作电压:75V;温度系数:±100ppm/°C;")
      (fields
        (field (name "Manufacturer Part") "0603WAF1001T5E")
        (field (name "Manufacturer") "UNI-ROYAL(厚声)")
      )
      (libsource (lib "easyedapro") (part "0603WAF1001T5E"))
    )
    (comp (ref "R62")
      (value "1kΩ")
      (footprint "easyedapro:R0603")
      (description "电阻类型:厚膜电阻;阻值:1kΩ;精度:±1%;功率:100mW;最大工作电压:75V;温度系数:±100ppm/°C;")
      (fields
        (field (name "Manufacturer Part") "0603WAF1001T5E")
        (field (name "Manufacturer") "UNI-ROYAL(厚声)")
      )
      (libsource (lib "easyedapro") (part "0603WAF1001T5E"))
    )
    (comp (ref "R63")
      (value "5.1kΩ")
      (footprint "easyedapro:R0603")
      (description "电阻类型:厚膜电阻;阻值:5.1kΩ;精度:±1%;功率:100mW;最大工作电压:75V;温度系数:±100ppm/°C;")
      (fields
        (field (name "Manufacturer Part") "0603WAF5101T5E")
        (field (name "Manufacturer") "UNI-ROYAL(厚声)")
      )
      (libsource (lib "easyedapro") (part "0603WAF5101T5E"))
    )
    (comp (ref "R64")
      (value "1kΩ")
      (footprint "easyedapro:R0603")
      (description "电阻类型:厚膜电阻;阻值:1kΩ;精度:±1%;功率:100mW;最大工作电压:75V;温度系数:±100ppm/°C;")
      (fields
        (field (name "Manufacturer Part") "0603WAF1001T5E")
        (field (name "Manufacturer") "UNI-ROYAL(厚声)")
      )
      (libsource (lib "easyedapro") (part "0603WAF1001T5E"))
    )
    (comp (ref "R65")
      (value "1kΩ")
      (footprint "easyedapro:R0603")
      (description "电阻类型:厚膜电阻;阻值:1kΩ;精度:±1%;功率:100mW;最大工作电压:75V;温度系数:±100ppm/°C;")
      (fields
        (field (name "Manufacturer Part") "0603WAF1001T5E")
        (field (name "Manufacturer") "UNI-ROYAL(厚声)")
      )
      (libsource (lib "easyedapro") (part "0603WAF1001T5E"))
    )
    (comp (ref "R66")
      (value "100Ω")
      (footprint "easyedapro:R0603")
      (description "电阻类型:厚膜电阻;阻值:100Ω;精度:±1%;功率:100mW;最大工作电压:75V;温度系数:±200ppm/°C;")
      (fields
        (field (name "Manufacturer Part") "0603WAF1000T5E")
        (field (name "Manufacturer") "UNI-ROYAL(厚声)")
      )
      (libsource (lib "easyedapro") (part "0603WAF1000T5E"))
    )
    (comp (ref "R67")
      (value "4.7Ω")
      (footprint "easyedapro:R0603")
      (description "电阻类型:厚膜电阻;阻值:4.7Ω;精度:±5%;功率:100mW;工作电压:75V;温度系数:±200ppm/°C;")
      (fields (field (name "Manufacturer Part") "FRC0603J4R7 TS") (field (name "Manufacturer") "FOJAN(富捷)"))
      (libsource (lib "easyedapro") (part "FRC0603J4R7 TS"))
    )
    (comp (ref "R68")
      (value "4.7Ω")
      (footprint "easyedapro:R0603")
      (description "电阻类型:厚膜电阻;阻值:4.7Ω;精度:±5%;功率:100mW;工作电压:75V;温度系数:±200ppm/°C;")
      (fields (field (name "Manufacturer Part") "FRC0603J4R7 TS") (field (name "Manufacturer") "FOJAN(富捷)"))
      (libsource (lib "easyedapro") (part "FRC0603J4R7 TS"))
    )
    (comp (ref "R69")
      (value "4.7Ω")
      (footprint "easyedapro:R0603")
      (description "电阻类型:厚膜电阻;阻值:4.7Ω;精度:±5%;功率:100mW;工作电压:75V;温度系数:±200ppm/°C;")
      (fields (field (name "Manufacturer Part") "FRC0603J4R7 TS") (field (name "Manufacturer") "FOJAN(富捷)"))
      (libsource (lib "easyedapro") (part "FRC0603J4R7 TS"))
    )
    (comp (ref "R70")
      (value "4.7Ω")
      (footprint "easyedapro:R0603")
      (description "电阻类型:厚膜电阻;阻值:4.7Ω;精度:±5%;功率:100mW;工作电压:75V;温度系数:±200ppm/°C;")
      (fields (field (name "Manufacturer Part") "FRC0603J4R7 TS") (field (name "Manufacturer") "FOJAN(富捷)"))
      (libsource (lib "easyedapro") (part "FRC0603J4R7 TS"))
    )
    (comp (ref "R71")
      (value "4.7Ω")
      (footprint "easyedapro:R0603")
      (description "电阻类型:厚膜电阻;阻值:4.7Ω;精度:±5%;功率:100mW;工作电压:75V;温度系数:±200ppm/°C;")
      (fields (field (name "Manufacturer Part") "FRC0603J4R7 TS") (field (name "Manufacturer") "FOJAN(富捷)"))
      (libsource (lib "easyedapro") (part "FRC0603J4R7 TS"))
    )
    (comp (ref "R72")
      (value "4.7Ω")
      (footprint "easyedapro:R0603")
      (description "电阻类型:厚膜电阻;阻值:4.7Ω;精度:±5%;功率:100mW;工作电压:75V;温度系数:±200ppm/°C;")
      (fields (field (name "Manufacturer Part") "FRC0603J4R7 TS") (field (name "Manufacturer") "FOJAN(富捷)"))
      (libsource (lib "easyedapro") (part "FRC0603J4R7 TS"))
    )
    (comp (ref "TP1")
      (value "~")
      (footprint "easyedapro:Test-Point-0.5mm")
      (description "Test Point 测试点")
      (libsource (lib "easyedapro") (part "Test-Point"))
    )
    (comp (ref "TP2")
      (value "~")
      (footprint "easyedapro:Test-Point-0.5mm")
      (description "Test Point 测试点")
      (libsource (lib "easyedapro") (part "Test-Point"))
    )
    (comp (ref "TP3")
      (value "~")
      (footprint "easyedapro:Test-Point-0.5mm")
      (description "Test Point 测试点")
      (libsource (lib "easyedapro") (part "Test-Point"))
    )
    (comp (ref "TP11")
      (value "~")
      (footprint "easyedapro:Test-Point-0.5mm")
      (description "Test Point 测试点")
      (libsource (lib "easyedapro") (part "Test-Point"))
    )
    (comp (ref "TP12")
      (value "~")
      (footprint "easyedapro:Test-Point-0.5mm")
      (description "Test Point 测试点")
      (libsource (lib "easyedapro") (part "Test-Point"))
    )
    (comp (ref "TP13")
      (value "~")
      (footprint "easyedapro:Test-Point-0.5mm")
      (description "Test Point 测试点")
      (libsource (lib "easyedapro") (part "Test-Point"))
    )
    (comp (ref "TP14")
      (value "~")
      (footprint "easyedapro:Test-Point-0.5mm")
      (description "Test Point 测试点")
      (libsource (lib "easyedapro") (part "Test-Point"))
    )
    (comp (ref "U8")
      (value "STC32G12K128-35I-LQFP48")
      (footprint "easyedapro:LQFP-48_L7.0-W7.0-P0.50-LS9.0-BL")
      (fields (field (name "Manufacturer") "STC"))
      (libsource (lib "easyedapro") (part "STC32G12K128-35I-LQFP48"))
    )
    (comp (ref "U9")
      (value "SE8650K2-HF")
      (footprint "easyedapro:SOT-89-3_L4.5-W2.5-P1.50-LS4.2-BR")
      (description "输出类型:固定;工作电压:80V;输出电压:5V;输出电流:-;电源纹波抑制比(PSRR):-;输出极性:正极;")
      (fields (field (name "Manufacturer") "SEAWARD(思旺)"))
      (libsource (lib "easyedapro") (part "SE8650K2-HF"))
    )
    (comp (ref "U10")
      (value "FD6288Q")
      (footprint "easyedapro:QFN-24_L4.0-W4.0-P0.50-BL-EP2.6")
      (fields (field (name "Manufacturer") "Fortior Tech(峰岹)"))
      (libsource (lib "easyedapro") (part "FD6288Q_C328453"))
    )
    (comp (ref "C59")
      (value "100nF")
      (footprint "easyedapro:C0603")
      (description "容值:100nF;精度:±10%;额定电压:50V;材质(温度系数):X7R;")
      (fields
        (field (name "Manufacturer Part") "CGA0603X7R104K500JT")
        (field (name "Manufacturer") "HRE(芯声)")
      )
      (libsource (lib "easyedapro") (part "CGA0603X7R104K500JT"))
    )
    (comp (ref "C60")
      (value "100nF")
      (footprint "easyedapro:C0603")
      (description "容值:100nF;精度:±10%;额定电压:50V;材质(温度系数):X7R;")
      (fields
        (field (name "Manufacturer Part") "CGA0603X7R104K500JT")
        (field (name "Manufacturer") "HRE(芯声)")
      )
      (libsource (lib "easyedapro") (part "CGA0603X7R104K500JT"))
    )
    (comp (ref "C61")
      (value "10uF")
      (footprint "easyedapro:C0603")
      (description "容值:10uF;精度:±10%;额定电压:10V;温度系数:X5R;")
      (fields
        (field (name "Manufacturer Part") "CGA0603X5R106K100JT")
        (field (name "Manufacturer") "HRE(芯声)")
      )
      (libsource (lib "easyedapro") (part "CGA0603X5R106K100JT"))
    )
    (comp (ref "C62")
      (value "100nF")
      (footprint "easyedapro:C0603")
      (description "容值:100nF;精度:±10%;额定电压:50V;材质(温度系数):X7R;")
      (fields
        (field (name "Manufacturer Part") "CGA0603X7R104K500JT")
        (field (name "Manufacturer") "HRE(芯声)")
      )
      (libsource (lib "easyedapro") (part "CGA0603X7R104K500JT"))
    )
    (comp (ref "C63")
      (value "100nF")
      (footprint "easyedapro:C0603")
      (description "容值:100nF;精度:±10%;额定电压:50V;材质(温度系数):X7R;")
      (fields
        (field (name "Manufacturer Part") "CGA0603X7R104K500JT")
        (field (name "Manufacturer") "HRE(芯声)")
      )
      (libsource (lib "easyedapro") (part "CGA0603X7R104K500JT"))
    )
    (comp (ref "C64")
      (value "100nF")
      (footprint "easyedapro:C0603")
      (description "容值:100nF;精度:±10%;额定电压:50V;材质(温度系数):X7R;")
      (fields
        (field (name "Manufacturer Part") "CGA0603X7R104K500JT")
        (field (name "Manufacturer") "HRE(芯声)")
      )
      (libsource (lib "easyedapro") (part "CGA0603X7R104K500JT"))
    )
    (comp (ref "C65")
      (value "100nF")
      (footprint "easyedapro:C0603")
      (description "容值:100nF;精度:±10%;额定电压:50V;材质(温度系数):X7R;")
      (fields
        (field (name "Manufacturer Part") "CGA0603X7R104K500JT")
        (field (name "Manufacturer") "HRE(芯声)")
      )
      (libsource (lib "easyedapro") (part "CGA0603X7R104K500JT"))
    )
    (comp (ref "C66")
      (value "100nF")
      (footprint "easyedapro:C0603")
      (description "容值:100nF;精度:±10%;额定电压:50V;材质(温度系数):X7R;")
      (fields
        (field (name "Manufacturer Part") "CGA0603X7R104K500JT")
        (field (name "Manufacturer") "HRE(芯声)")
      )
      (libsource (lib "easyedapro") (part "CGA0603X7R104K500JT"))
    )
    (comp (ref "C77")
      (value "22uF")
      (footprint "easyedapro:C0805")
      (description "容值:22uF;精度:±20%;额定电压:25V;温度系数:X5R;")
      (fields
        (field (name "Manufacturer Part") "CGA0805X5R226M250MT")
        (field (name "Manufacturer") "HRE(芯声)")
      )
      (libsource (lib "easyedapro") (part "CGA0805X5R226M250MT"))
    )
    (comp (ref "C78")
      (value "4.7uF")
      (footprint "easyedapro:C0805")
      (description "容值:4.7uF;精度:±10%;额定电压:25V;材质(温度系数):X5R;")
      (fields
        (field (name "Manufacturer Part") "CL21A475KAQNNNE")
        (field (name "Manufacturer") "SAMSUNG(三星)")
      )
      (libsource (lib "easyedapro") (part "CL21A475KAQNNNE"))
    )
    (comp (ref "C79")
      (value "4.7uF")
      (footprint "easyedapro:C0805")
      (description "容值:4.7uF;精度:±10%;额定电压:25V;材质(温度系数):X5R;")
      (fields
        (field (name "Manufacturer Part") "CL21A475KAQNNNE")
        (field (name "Manufacturer") "SAMSUNG(三星)")
      )
      (libsource (lib "easyedapro") (part "CL21A475KAQNNNE"))
    )
    (comp (ref "C80")
      (value "4.7uF")
      (footprint "easyedapro:C0805")
      (description "容值:4.7uF;精度:±10%;额定电压:25V;材质(温度系数):X5R;")
      (fields
        (field (name "Manufacturer Part") "CL21A475KAQNNNE")
        (field (name "Manufacturer") "SAMSUNG(三星)")
      )
      (libsource (lib "easyedapro") (part "CL21A475KAQNNNE"))
    )
    (comp (ref "D16")
      (value "B5819WS")
      (footprint "easyedapro:SOD-323_L1.7-W1.3-LS2.5-FD")
      (description "二极管配置:独立式;正向压降(Vf):600mV@1.0A;直流反向耐压(Vr):40V;整流电流:1A;")
      (fields (field (name "Manufacturer") "宏迦橙"))
      (libsource (lib "easyedapro") (part "B5819WS_C7420331"))
    )
    (comp (ref "D17")
      (value "B5819WS")
      (footprint "easyedapro:SOD-323_L1.7-W1.3-LS2.5-FD")
      (description "二极管配置:独立式;正向压降(Vf):600mV@1.0A;直流反向耐压(Vr):40V;整流电流:1A;")
      (fields (field (name "Manufacturer") "宏迦橙"))
      (libsource (lib "easyedapro") (part "B5819WS_C7420331"))
    )
    (comp (ref "D18")
      (value "B5819WS")
      (footprint "easyedapro:SOD-323_L1.7-W1.3-LS2.5-FD")
      (description "二极管配置:独立式;正向压降(Vf):600mV@1.0A;直流反向耐压(Vr):40V;整流电流:1A;")
      (fields (field (name "Manufacturer") "宏迦橙"))
      (libsource (lib "easyedapro") (part "B5819WS_C7420331"))
    )
    (comp (ref "D19")
      (value "BZT52C15")
      (footprint "easyedapro:SOD-123_L2.7-W1.6-LS3.7-RD")
      (description "二极管配置:独立式;稳压值(标称值):15V;稳压值(范围):14.25V~15.75V;耗散功率(Pd):500mW;")
      (fields (field (name "Manufacturer") "宏嘉诚"))
      (libsource (lib "easyedapro") (part "BZT52C15_C19077412"))
    )
    (comp (ref "L2")
      (value "MLB1608F-000T")
      (footprint "easyedapro:L0603")
      (description "阻抗@频率:0Ω@100MHz;误差:±25%;直流电阻(DCR):-;")
      (fields (field (name "Manufacturer") "MetalLions(美铼)"))
      (libsource (lib "easyedapro") (part "MLB1608F-000T"))
    )
    (comp (ref "LED7")
      (value "NCD0603R1")
      (footprint "easyedapro:LED0603-RD_RED")
      (fields (field (name "Manufacturer") "国星光电"))
      (libsource (lib "easyedapro") (part "FC-DA1608HRK-620D"))
    )
    (comp (ref "Q18")
      (value "TPN2R805PL,L1Q")
      (footprint "easyedapro:TSON-8_L3.1-W3.1-P0.65-LS3.3-BL-EP")
      (fields (field (name "Manufacturer") "TOSHIBA(东芝)"))
      (libsource (lib "easyedapro") (part "TPN2R805PL,L1Q"))
    )
    (comp (ref "Q19")
      (value "TPN2R805PL,L1Q")
      (footprint "easyedapro:TSON-8_L3.1-W3.1-P0.65-LS3.3-BL-EP")
      (fields (field (name "Manufacturer") "TOSHIBA(东芝)"))
      (libsource (lib "easyedapro") (part "TPN2R805PL,L1Q"))
    )
    (comp (ref "Q20")
      (value "TPN2R805PL,L1Q")
      (footprint "easyedapro:TSON-8_L3.1-W3.1-P0.65-LS3.3-BL-EP")
      (fields (field (name "Manufacturer") "TOSHIBA(东芝)"))
      (libsource (lib "easyedapro") (part "TPN2R805PL,L1Q"))
    )
    (comp (ref "Q21")
      (value "TPN2R805PL,L1Q")
      (footprint "easyedapro:TSON-8_L3.1-W3.1-P0.65-LS3.3-BL-EP")
      (fields (field (name "Manufacturer") "TOSHIBA(东芝)"))
      (libsource (lib "easyedapro") (part "TPN2R805PL,L1Q"))
    )
    (comp (ref "Q22")
      (value "TPN2R805PL,L1Q")
      (footprint "easyedapro:TSON-8_L3.1-W3.1-P0.65-LS3.3-BL-EP")
      (fields (field (name "Manufacturer") "TOSHIBA(东芝)"))
      (libsource (lib "easyedapro") (part "TPN2R805PL,L1Q"))
    )
    (comp (ref "Q23")
      (value "TPN2R805PL,L1Q")
      (footprint "easyedapro:TSON-8_L3.1-W3.1-P0.65-LS3.3-BL-EP")
      (fields (field (name "Manufacturer") "TOSHIBA(东芝)"))
      (libsource (lib "easyedapro") (part "TPN2R805PL,L1Q"))
    )
    (comp (ref "R73")
      (value "47kΩ")
      (footprint "easyedapro:R0603")
      (description "电阻类型:厚膜电阻;阻值:47kΩ;精度:±1%;功率:100mW;最大工作电压:75V;温度系数:±100ppm/°C;")
      (fields
        (field (name "Manufacturer Part") "0603WAF4702T5E")
        (field (name "Manufacturer") "UNI-ROYAL(厚声)")
      )
      (libsource (lib "easyedapro") (part "0603WAF4702T5E"))
    )
    (comp (ref "R74")
      (value "10kΩ")
      (footprint "easyedapro:R0603")
      (description "电阻类型:厚膜电阻;阻值:10kΩ;精度:±5%;功率:100mW;最大工作电压:75V;温度系数:±100ppm/°C;")
      (fields (field (name "Manufacturer Part") "FRC0603J103TS") (field (name "Manufacturer") "FOJAN(富捷)"))
      (libsource (lib "easyedapro") (part "FRC0603J103TS"))
    )
    (comp (ref "R75")
      (value "10kΩ")
      (footprint "easyedapro:R0603")
      (description "电阻类型:厚膜电阻;阻值:10kΩ;精度:±5%;功率:100mW;最大工作电压:75V;温度系数:±100ppm/°C;")
      (fields (field (name "Manufacturer Part") "FRC0603J103TS") (field (name "Manufacturer") "FOJAN(富捷)"))
      (libsource (lib "easyedapro") (part "FRC0603J103TS"))
    )
    (comp (ref "R76")
      (value "5.1kΩ")
      (footprint "easyedapro:R0603")
      (description "电阻类型:厚膜电阻;阻值:5.1kΩ;精度:±1%;功率:100mW;最大工作电压:75V;温度系数:±100ppm/°C;")
      (fields
        (field (name "Manufacturer Part") "0603WAF5101T5E")
        (field (name "Manufacturer") "UNI-ROYAL(厚声)")
      )
      (libsource (lib "easyedapro") (part "0603WAF5101T5E"))
    )
    (comp (ref "R77")
      (value "1kΩ")
      (footprint "easyedapro:R0603")
      (description "电阻类型:厚膜电阻;阻值:1kΩ;精度:±1%;功率:100mW;最大工作电压:75V;温度系数:±100ppm/°C;")
      (fields
        (field (name "Manufacturer Part") "0603WAF1001T5E")
        (field (name "Manufacturer") "UNI-ROYAL(厚声)")
      )
      (libsource (lib "easyedapro") (part "0603WAF1001T5E"))
    )
    (comp (ref "R78")
      (value "1kΩ")
      (footprint "easyedapro:R0603")
      (description "电阻类型:厚膜电阻;阻值:1kΩ;精度:±1%;功率:100mW;最大工作电压:75V;温度系数:±100ppm/°C;")
      (fields
        (field (name "Manufacturer Part") "0603WAF1001T5E")
        (field (name "Manufacturer") "UNI-ROYAL(厚声)")
      )
      (libsource (lib "easyedapro") (part "0603WAF1001T5E"))
    )
    (comp (ref "R79")
      (value "5.1kΩ")
      (footprint "easyedapro:R0603")
      (description "电阻类型:厚膜电阻;阻值:5.1kΩ;精度:±1%;功率:100mW;最大工作电压:75V;温度系数:±100ppm/°C;")
      (fields
        (field (name "Manufacturer Part") "0603WAF5101T5E")
        (field (name "Manufacturer") "UNI-ROYAL(厚声)")
      )
      (libsource (lib "easyedapro") (part "0603WAF5101T5E"))
    )
    (comp (ref "R80")
      (value "1kΩ")
      (footprint "easyedapro:R0603")
      (description "电阻类型:厚膜电阻;阻值:1kΩ;精度:±1%;功率:100mW;最大工作电压:75V;温度系数:±100ppm/°C;")
      (fields
        (field (name "Manufacturer Part") "0603WAF1001T5E")
        (field (name "Manufacturer") "UNI-ROYAL(厚声)")
      )
      (libsource (lib "easyedapro") (part "0603WAF1001T5E"))
    )
    (comp (ref "R81")
      (value "1kΩ")
      (footprint "easyedapro:R0603")
      (description "电阻类型:厚膜电阻;阻值:1kΩ;精度:±1%;功率:100mW;最大工作电压:75V;温度系数:±100ppm/°C;")
      (fields
        (field (name "Manufacturer Part") "0603WAF1001T5E")
        (field (name "Manufacturer") "UNI-ROYAL(厚声)")
      )
      (libsource (lib "easyedapro") (part "0603WAF1001T5E"))
    )
    (comp (ref "R82")
      (value "5.1kΩ")
      (footprint "easyedapro:R0603")
      (description "电阻类型:厚膜电阻;阻值:5.1kΩ;精度:±1%;功率:100mW;最大工作电压:75V;温度系数:±100ppm/°C;")
      (fields
        (field (name "Manufacturer Part") "0603WAF5101T5E")
        (field (name "Manufacturer") "UNI-ROYAL(厚声)")
      )
      (libsource (lib "easyedapro") (part "0603WAF5101T5E"))
    )
    (comp (ref "R83")
      (value "1kΩ")
      (footprint "easyedapro:R0603")
      (description "电阻类型:厚膜电阻;阻值:1kΩ;精度:±1%;功率:100mW;最大工作电压:75V;温度系数:±100ppm/°C;")
      (fields
        (field (name "Manufacturer Part") "0603WAF1001T5E")
        (field (name "Manufacturer") "UNI-ROYAL(厚声)")
      )
      (libsource (lib "easyedapro") (part "0603WAF1001T5E"))
    )
    (comp (ref "R84")
      (value "1kΩ")
      (footprint "easyedapro:R0603")
      (description "电阻类型:厚膜电阻;阻值:1kΩ;精度:±1%;功率:100mW;最大工作电压:75V;温度系数:±100ppm/°C;")
      (fields
        (field (name "Manufacturer Part") "0603WAF1001T5E")
        (field (name "Manufacturer") "UNI-ROYAL(厚声)")
      )
      (libsource (lib "easyedapro") (part "0603WAF1001T5E"))
    )
    (comp (ref "R85")
      (value "100Ω")
      (footprint "easyedapro:R0603")
      (description "电阻类型:厚膜电阻;阻值:100Ω;精度:±1%;功率:100mW;最大工作电压:75V;温度系数:±200ppm/°C;")
      (fields
        (field (name "Manufacturer Part") "0603WAF1000T5E")
        (field (name "Manufacturer") "UNI-ROYAL(厚声)")
      )
      (libsource (lib "easyedapro") (part "0603WAF1000T5E"))
    )
    (comp (ref "R86")
      (value "4.7Ω")
      (footprint "easyedapro:R0603")
      (description "电阻类型:厚膜电阻;阻值:4.7Ω;精度:±5%;功率:100mW;工作电压:75V;温度系数:±200ppm/°C;")
      (fields (field (name "Manufacturer Part") "FRC0603J4R7 TS") (field (name "Manufacturer") "FOJAN(富捷)"))
      (libsource (lib "easyedapro") (part "FRC0603J4R7 TS"))
    )
    (comp (ref "R87")
      (value "4.7Ω")
      (footprint "easyedapro:R0603")
      (description "电阻类型:厚膜电阻;阻值:4.7Ω;精度:±5%;功率:100mW;工作电压:75V;温度系数:±200ppm/°C;")
      (fields (field (name "Manufacturer Part") "FRC0603J4R7 TS") (field (name "Manufacturer") "FOJAN(富捷)"))
      (libsource (lib "easyedapro") (part "FRC0603J4R7 TS"))
    )
    (comp (ref "R88")
      (value "4.7Ω")
      (footprint "easyedapro:R0603")
      (description "电阻类型:厚膜电阻;阻值:4.7Ω;精度:±5%;功率:100mW;工作电压:75V;温度系数:±200ppm/°C;")
      (fields (field (name "Manufacturer Part") "FRC0603J4R7 TS") (field (name "Manufacturer") "FOJAN(富捷)"))
      (libsource (lib "easyedapro") (part "FRC0603J4R7 TS"))
    )
    (comp (ref "R89")
      (value "4.7Ω")
      (footprint "easyedapro:R0603")
      (description "电阻类型:厚膜电阻;阻值:4.7Ω;精度:±5%;功率:100mW;工作电压:75V;温度系数:±200ppm/°C;")
      (fields (field (name "Manufacturer Part") "FRC0603J4R7 TS") (field (name "Manufacturer") "FOJAN(富捷)"))
      (libsource (lib "easyedapro") (part "FRC0603J4R7 TS"))
    )
    (comp (ref "R90")
      (value "4.7Ω")
      (footprint "easyedapro:R0603")
      (description "电阻类型:厚膜电阻;阻值:4.7Ω;精度:±5%;功率:100mW;工作电压:75V;温度系数:±200ppm/°C;")
      (fields (field (name "Manufacturer Part") "FRC0603J4R7 TS") (field (name "Manufacturer") "FOJAN(富捷)"))
      (libsource (lib "easyedapro") (part "FRC0603J4R7 TS"))
    )
    (comp (ref "R91")
      (value "4.7Ω")
      (footprint "easyedapro:R0603")
      (description "电阻类型:厚膜电阻;阻值:4.7Ω;精度:±5%;功率:100mW;工作电压:75V;温度系数:±200ppm/°C;")
      (fields (field (name "Manufacturer Part") "FRC0603J4R7 TS") (field (name "Manufacturer") "FOJAN(富捷)"))
      (libsource (lib "easyedapro") (part "FRC0603J4R7 TS"))
    )
    (comp (ref "TP4")
      (value "~")
      (footprint "easyedapro:Test-Point-0.5mm")
      (description "Test Point 测试点")
      (libsource (lib "easyedapro") (part "Test-Point"))
    )
    (comp (ref "TP5")
      (value "~")
      (footprint "easyedapro:Test-Point-0.5mm")
      (description "Test Point 测试点")
      (libsource (lib "easyedapro") (part "Test-Point"))
    )
    (comp (ref "TP6")
      (value "~")
      (footprint "easyedapro:Test-Point-0.5mm")
      (description "Test Point 测试点")
      (libsource (lib "easyedapro") (part "Test-Point"))
    )
    (comp (ref "TP7")
      (value "~")
      (footprint "easyedapro:Test-Point-0.5mm")
      (description "Test Point 测试点")
      (libsource (lib "easyedapro") (part "Test-Point"))
    )
    (comp (ref "TP8")
      (value "~")
      (footprint "easyedapro:Test-Point-0.5mm")
      (description "Test Point 测试点")
      (libsource (lib "easyedapro") (part "Test-Point"))
    )
    (comp (ref "TP9")
      (value "~")
      (footprint "easyedapro:Test-Point-0.5mm")
      (description "Test Point 测试点")
      (libsource (lib "easyedapro") (part "Test-Point"))
    )
    (comp (ref "TP10")
      (value "~")
      (footprint "easyedapro:Test-Point-0.5mm")
      (description "Test Point 测试点")
      (libsource (lib "easyedapro") (part "Test-Point"))
    )
    (comp (ref "U17")
      (value "STC32G12K128-35I-LQFP48")
      (footprint "easyedapro:LQFP-48_L7.0-W7.0-P0.50-LS9.0-BL")
      (fields (field (name "Manufacturer") "STC"))
      (libsource (lib "easyedapro") (part "STC32G12K128-35I-LQFP48"))
    )
    (comp (ref "U19")
      (value "FD6288Q")
      (footprint "easyedapro:QFN-24_L4.0-W4.0-P0.50-BL-EP2.6")
      (fields (field (name "Manufacturer") "Fortior Tech(峰岹)"))
      (libsource (lib "easyedapro") (part "FD6288Q_C328453"))
    )
  )
  (nets
    (net (code "1") (name "+5V") (class "Default")
      (node (ref "C33") (pin "2") (pinfunction "2_2") (pintype "unspecified"))
      (node (ref "C34") (pin "2") (pinfunction "2_2") (pintype "unspecified"))
      (node (ref "C53") (pin "1") (pinfunction "1_1") (pintype "unspecified"))
      (node (ref "C54") (pin "1") (pinfunction "1_1") (pintype "unspecified"))
      (node (ref "C60") (pin "2") (pinfunction "2_2") (pintype "unspecified"))
      (node (ref "C61") (pin "2") (pinfunction "2_2") (pintype "unspecified"))
      (node (ref "L1") (pin "2") (pinfunction "2_2") (pintype "unspecified"))
      (node (ref "L2") (pin "2") (pinfunction "2_2") (pintype "unspecified"))
      (node (ref "LED6") (pin "2") (pinfunction "A_2") (pintype "input"))
      (node (ref "LED7") (pin "2") (pinfunction "A_2") (pintype "input"))
      (node (ref "TP10") (pin "1") (pinfunction "1_1") (pintype "input"))
      (node (ref "TP14") (pin "1") (pinfunction "1_1") (pintype "input"))
      (node (ref "U17") (pin "15") (pinfunction "VCC/AVCC_15") (pintype "unspecified"))
      (node (ref "U8") (pin "15") (pinfunction "VCC/AVCC_15") (pintype "unspecified"))
      (node (ref "U9") (pin "3") (pinfunction "VOUT_3") (pintype "unspecified"))
    )
    (net (code "2") (name "ABMF1") (class "Default")
      (node (ref "C37") (pin "2") (pinfunction "2_2") (pintype "unspecified"))
      (node (ref "R53") (pin "1") (pinfunction "1_1") (pintype "input"))
      (node (ref "R56") (pin "1") (pinfunction "1_1") (pintype "input"))
      (node (ref "R59") (pin "2") (pinfunction "2_2") (pintype "input"))
      (node (ref "U8") (pin "28") (pinfunction "CMP+/TXD_2/INT3/P3.7_28") (pintype "unspecified"))
    )
    (net (code "3") (name "ABMF2") (class "Default")
      (node (ref "C64") (pin "2") (pinfunction "2_2") (pintype "unspecified"))
      (node (ref "R76") (pin "1") (pinfunction "1_1") (pintype "input"))
      (node (ref "R77") (pin "1") (pinfunction "1_1") (pintype "input"))
      (node (ref "R78") (pin "2") (pinfunction "2_2") (pintype "input"))
      (node (ref "U17") (pin "28") (pinfunction "CMP+/TXD_2/INT3/P3.7_28") (pintype "unspecified"))
    )
    (net (code "4") (name "BATADC1") (class "Default")
      (node (ref "C36") (pin "2") (pinfunction "2_2") (pintype "unspecified"))
      (node (ref "R50") (pin "1") (pinfunction "1_1") (pintype "input"))
      (node (ref "R51") (pin "2") (pinfunction "2_2") (pintype "unspecified"))
      (node (ref "U8") (pin "46") (pinfunction "LINTX/CAN2_TX/PWM8_3/TXD4/ADC11/AD3/P0.3_46") (pintype "unspecified"))
    )
    (net (code "5") (name "BATADC2") (class "Default")
      (node (ref "C63") (pin "2") (pinfunction "2_2") (pintype "unspecified"))
      (node (ref "R73") (pin "1") (pinfunction "1_1") (pintype "input"))
      (node (ref "R74") (pin "2") (pinfunction "2_2") (pintype "unspecified"))
      (node (ref "U17") (pin "46") (pinfunction "LINTX/CAN2_TX/PWM8_3/TXD4/ADC11/AD3/P0.3_46") (pintype "unspecified"))
    )
    (net (code "6") (name "BBMF1") (class "Default")
      (node (ref "C38") (pin "2") (pinfunction "2_2") (pintype "unspecified"))
      (node (ref "R60") (pin "1") (pinfunction "1_1") (pintype "input"))
      (node (ref "R61") (pin "1") (pinfunction "1_1") (pintype "input"))
      (node (ref "R62") (pin "2") (pinfunction "2_2") (pintype "input"))
      (node (ref "U8") (pin "25") (pinfunction "CAN_TX_2/CMP+_3/TXD3_2/P5.1_25") (pintype "unspecified"))
    )
    (net (code "7") (name "BBMF2") (class "Default")
      (node (ref "C65") (pin "2") (pinfunction "2_2") (pintype "unspecified"))
      (node (ref "R79") (pin "1") (pinfunction "1_1") (pintype "input"))
      (node (ref "R80") (pin "1") (pinfunction "1_1") (pintype "input"))
      (node (ref "R81") (pin "2") (pinfunction "2_2") (pintype "input"))
      (node (ref "U17") (pin "25") (pinfunction "CAN_TX_2/CMP+_3/TXD3_2/P5.1_25") (pintype "unspecified"))
    )
    (net (code "8") (name "CBMF1") (class "Default")
      (node (ref "C39") (pin "2") (pinfunction "2_2") (pintype "unspecified"))
      (node (ref "R63") (pin "1") (pinfunction "1_1") (pintype "input"))
      (node (ref "R64") (pin "1") (pinfunction "1_1") (pintype "input"))
      (node (ref "R65") (pin "2") (pinfunction "2_2") (pintype "input"))
      (node (ref "U8") (pin "24") (pinfunction "P5.0/RXD3_2/CMP+_2/CAN_RX_2_24") (pintype "unspecified"))
    )
    (net (code "9") (name "CBMF2") (class "Default")
      (node (ref "C66") (pin "2") (pinfunction "2_2") (pintype "unspecified"))
      (node (ref "R82") (pin "1") (pinfunction "1_1") (pintype "input"))
      (node (ref "R83") (pin "1") (pinfunction "1_1") (pintype "input"))
      (node (ref "R84") (pin "2") (pinfunction "2_2") (pintype "input"))
      (node (ref "U17") (pin "24") (pinfunction "P5.0/RXD3_2/CMP+_2/CAN_RX_2_24") (pintype "unspecified"))
    )
    (net (code "10") (name "DBRX1") (class "Default")
      (node (ref "TP12") (pin "1") (pinfunction "1_1") (pintype "input"))
      (node (ref "U8") (pin "19") (pinfunction "P3.0/D-/RXD/INT4_19") (pintype "unspecified"))
    )
    (net (code "11") (name "DBRX2") (class "Default")
      (node (ref "TP8") (pin "1") (pinfunction "1_1") (pintype "input"))
      (node (ref "U17") (pin "19") (pinfunction "P3.0/D-/RXD/INT4_19") (pintype "unspecified"))
    )
    (net (code "12") (name "DBTX1") (class "Default")
      (node (ref "TP11") (pin "1") (pinfunction "1_1") (pintype "input"))
      (node (ref "U8") (pin "20") (pinfunction "P3.1/D+/TXD_20") (pintype "unspecified"))
    )
    (net (code "13") (name "DBTX2") (class "Default")
      (node (ref "TP7") (pin "1") (pinfunction "1_1") (pintype "input"))
      (node (ref "U17") (pin "20") (pinfunction "P3.1/D+/TXD_20") (pintype "unspecified"))
    )
    (net (code "14") (name "DVDD") (class "Default")
      (node (ref "C28") (pin "2") (pinfunction "2_2") (pintype "unspecified"))
      (node (ref "U4") (pin "8") (pinfunction "DVDD_8") (pintype "unspecified"))
      (node (ref "U6") (pin "14") (pinfunction "VCC_14") (pintype "unspecified"))
    )
    (net (code "15") (name "EN_1") (class "Default")
      (node (ref "U4") (pin "14") (pinfunction "EN_14") (pintype "unspecified"))
      (node (ref "U6") (pin "6") (pinfunction "2Y_6") (pintype "unspecified"))
    )
    (net (code "16") (name "EN_2") (class "Default")
      (node (ref "U5") (pin "14") (pinfunction "EN_14") (pintype "unspecified"))
      (node (ref "U6") (pin "8") (pinfunction "3Y_8") (pintype "unspecified"))
    )
    (net (code "17") (name "GND") (class "Default")
      (node (ref "C18") (pin "1") (pinfunction "1_1") (pintype "unspecified"))
      (node (ref "C19") (pin "1") (pinfunction "1_1") (pintype "unspecified"))
      (node (ref "C22") (pin "1") (pinfunction "1_1") (pintype "unspecified"))
      (node (ref "C23") (pin "1") (pinfunction "1_1") (pintype "unspecified"))
      (node (ref "C24") (pin "1") (pinfunction "1_1") (pintype "unspecified"))
      (node (ref "C27") (pin "1") (pinfunction "1_1") (pintype "unspecified"))
      (node (ref "C28") (pin "1") (pinfunction "1_1") (pintype "unspecified"))
      (node (ref "C29") (pin "1") (pinfunction "1_1") (pintype "unspecified"))
      (node (ref "C30") (pin "1") (pinfunction "1_1") (pintype "unspecified"))
      (node (ref "C31") (pin "2") (pinfunction "2_2") (pintype "input"))
      (node (ref "C32") (pin "1") (pinfunction "1_1") (pintype "unspecified"))
      (node (ref "C33") (pin "1") (pinfunction "1_1") (pintype "unspecified"))
      (node (ref "C34") (pin "1") (pinfunction "1_1") (pintype "unspecified"))
      (node (ref "C35") (pin "1") (pinfunction "1_1") (pintype "unspecified"))
      (node (ref "C36") (pin "1") (pinfunction "1_1") (pintype "unspecified"))
      (node (ref "C37") (pin "1") (pinfunction "1_1") (pintype "unspecified"))
      (node (ref "C38") (pin "1") (pinfunction "1_1") (pintype "unspecified"))
      (node (ref "C39") (pin "1") (pinfunction "1_1") (pintype "unspecified"))
      (node (ref "C40") (pin "1") (pinfunction "1_1") (pintype "unspecified"))
      (node (ref "C46") (pin "2") (pinfunction "2_2") (pintype "input"))
      (node (ref "C47") (pin "1") (pinfunction "1_1") (pintype "unspecified"))
      (node (ref "C48") (pin "1") (pinfunction "1_1") (pintype "unspecified"))
      (node (ref "C49") (pin "1") (pinfunction "1_1") (pintype "unspecified"))
      (node (ref "C50") (pin "1") (pinfunction "1_1") (pintype "unspecified"))
      (node (ref "C51") (pin "1") (pinfunction "1_1") (pintype "unspecified"))
      (node (ref "C52") (pin "1") (pinfunction "1_1") (pintype "unspecified"))
      (node (ref "C53") (pin "2") (pinfunction "2_2") (pintype "unspecified"))
      (node (ref "C54") (pin "2") (pinfunction "2_2") (pintype "unspecified"))
      (node (ref "C55") (pin "2") (pinfunction "2_2") (pintype "unspecified"))
      (node (ref "C59") (pin "1") (pinfunction "1_1") (pintype "unspecified"))
      (node (ref "C60") (pin "1") (pinfunction "1_1") (pintype "unspecified"))
      (node (ref "C61") (pin "1") (pinfunction "1_1") (pintype "unspecified"))
      (node (ref "C62") (pin "1") (pinfunction "1_1") (pintype "unspecified"))
      (node (ref "C63") (pin "1") (pinfunction "1_1") (pintype "unspecified"))
      (node (ref "C64") (pin "1") (pinfunction "1_1") (pintype "unspecified"))
      (node (ref "C65") (pin "1") (pinfunction "1_1") (pintype "unspecified"))
      (node (ref "C66") (pin "1") (pinfunction "1_1") (pintype "unspecified"))
      (node (ref "C77") (pin "2") (pinfunction "2_2") (pintype "unspecified"))
      (node (ref "CN11") (pin "3") (pinfunction "3_3") (pintype "unspecified"))
      (node (ref "CN11") (pin "4") (pinfunction "4_4") (pintype "unspecified"))
      (node (ref "CN13") (pin "2") (pinfunction "2_2") (pintype "unspecified"))
      (node (ref "CN13") (pin "5") (pinfunction "5_5") (pintype "unspecified"))
      (node (ref "CN7") (pin "3") (pinfunction "3_3") (pintype "unspecified"))
      (node (ref "CN7") (pin "4") (pinfunction "4_4") (pintype "unspecified"))
      (node (ref "CN8") (pin "3") (pinfunction "3_3") (pintype "unspecified"))
      (node (ref "CN8") (pin "4") (pinfunction "4_4") (pintype "unspecified"))
      (node (ref "CN9") (pin "1") (pinfunction "-_1") (pintype "unspecified"))
      (node (ref "CN9") (pin "3") (pinfunction "3_3") (pintype "unspecified"))
      (node (ref "CN9") (pin "4") (pinfunction "4_4") (pintype "unspecified"))
      (node (ref "D12") (pin "2") (pinfunction "A_2") (pintype "unspecified"))
      (node (ref "D19") (pin "2") (pinfunction "A_2") (pintype "unspecified"))
      (node (ref "LED4") (pin "1") (pinfunction "K_1") (pintype "input"))
      (node (ref "LED5") (pin "1") (pinfunction "-_1") (pintype "input"))
      (node (ref "Q10") (pin "1") (pinfunction "S_1") (pintype "unspecified"))
      (node (ref "Q10") (pin "2") (pinfunction "S_2") (pintype "unspecified"))
      (node (ref "Q10") (pin "3") (pinfunction "S_3") (pintype "unspecified"))
      (node (ref "Q15") (pin "1") (pinfunction "S_1") (pintype "unspecified"))
      (node (ref "Q15") (pin "2") (pinfunction "S_2") (pintype "unspecified"))
      (node (ref "Q15") (pin "3") (pinfunction "S_3") (pintype "unspecified"))
      (node (ref "Q16") (pin "1") (pinfunction "S_1") (pintype "unspecified"))
      (node (ref "Q16") (pin "2") (pinfunction "S_2") (pintype "unspecified"))
      (node (ref "Q16") (pin "3") (pinfunction "S_3") (pintype "unspecified"))
      (node (ref "Q17") (pin "1") (pinfunction "S_1") (pintype "unspecified"))
      (node (ref "Q17") (pin "2") (pinfunction "S_2") (pintype "unspecified"))
      (node (ref "Q17") (pin "3") (pinfunction "S_3") (pintype "unspecified"))
      (node (ref "Q21") (pin "1") (pinfunction "S_1") (pintype "unspecified"))
      (node (ref "Q21") (pin "2") (pinfunction "S_2") (pintype "unspecified"))
      (node (ref "Q21") (pin "3") (pinfunction "S_3") (pintype "unspecified"))
      (node (ref "Q22") (pin "1") (pinfunction "S_1") (pintype "unspecified"))
      (node (ref "Q22") (pin "2") (pinfunction "S_2") (pintype "unspecified"))
      (node (ref "Q22") (pin "3") (pinfunction "S_3") (pintype "unspecified"))
      (node (ref "Q23") (pin "1") (pinfunction "S_1") (pintype "unspecified"))
      (node (ref "Q23") (pin "2") (pinfunction "S_2") (pintype "unspecified"))
      (node (ref "Q23") (pin "3") (pinfunction "S_3") (pintype "unspecified"))
      (node (ref "Q5") (pin "1") (pinfunction "S_1") (pintype "unspecified"))
      (node (ref "Q5") (pin "2") (pinfunction "S_2") (pintype "unspecified"))
      (node (ref "Q5") (pin "3") (pinfunction "S_3") (pintype "unspecified"))
      (node (ref "Q6") (pin "1") (pinfunction "S_1") (pintype "unspecified"))
      (node (ref "Q6") (pin "2") (pinfunction "S_2") (pintype "unspecified"))
      (node (ref "Q6") (pin "3") (pinfunction "S_3") (pintype "unspecified"))
      (node (ref "Q9") (pin "1") (pinfunction "S_1") (pintype "unspecified"))
      (node (ref "Q9") (pin "2") (pinfunction "S_2") (pintype "unspecified"))
      (node (ref "Q9") (pin "3") (pinfunction "S_3") (pintype "unspecified"))
      (node (ref "R44") (pin "2") (pinfunction "2_2") (pintype "unspecified"))
      (node (ref "R45") (pin "1") (pinfunction "1_1") (pintype "unspecified"))
      (node (ref "R46") (pin "2") (pinfunction "2_2") (pintype "unspecified"))
      (node (ref "R47") (pin "1") (pinfunction "1_1") (pintype "unspecified"))
      (node (ref "R51") (pin "1") (pinfunction "1_1") (pintype "unspecified"))
      (node (ref "R59") (pin "1") (pinfunction "1_1") (pintype "input"))
      (node (ref "R62") (pin "1") (pinfunction "1_1") (pintype "input"))
      (node (ref "R65") (pin "1") (pinfunction "1_1") (pintype "input"))
      (node (ref "R74") (pin "1") (pinfunction "1_1") (pintype "unspecified"))
      (node (ref "R78") (pin "1") (pinfunction "1_1") (pintype "input"))
      (node (ref "R81") (pin "1") (pinfunction "1_1") (pintype "input"))
      (node (ref "R84") (pin "1") (pinfunction "1_1") (pintype "input"))
      (node (ref "SW2") (pin "0") (pinfunction "0_0") (pintype "unspecified"))
      (node (ref "TP13") (pin "1") (pinfunction "1_1") (pintype "input"))
      (node (ref "TP9") (pin "1") (pinfunction "1_1") (pintype "input"))
      (node (ref "U10") (pin "25") (pinfunction "EP_25") (pintype "unspecified"))
      (node (ref "U10") (pin "6") (pinfunction "COM_6") (pintype "unspecified"))
      (node (ref "U17") (pin "17") (pinfunction "GND/AGND/Vref-_17") (pintype "unspecified"))
      (node (ref "U19") (pin "25") (pinfunction "EP_25") (pintype "unspecified"))
      (node (ref "U19") (pin "6") (pinfunction "COM_6") (pintype "unspecified"))
      (node (ref "U4") (pin "16") (pinfunction "GND_16") (pintype "unspecified"))
      (node (ref "U4") (pin "20") (pinfunction "SN_20") (pintype "unspecified"))
      (node (ref "U4") (pin "21") (pinfunction "SP_21") (pintype "unspecified"))
      (node (ref "U4") (pin "25") (pinfunction "EP_25") (pintype "unspecified"))
      (node (ref "U4") (pin "5") (pinfunction "GND_5") (pintype "unspecified"))
      (node (ref "U5") (pin "16") (pinfunction "GND_16") (pintype "unspecified"))
      (node (ref "U5") (pin "20") (pinfunction "SN_20") (pintype "unspecified"))
      (node (ref "U5") (pin "21") (pinfunction "SP_21") (pintype "unspecified"))
      (node (ref "U5") (pin "25") (pinfunction "EP_25") (pintype "unspecified"))
      (node (ref "U5") (pin "5") (pinfunction "GND_5") (pintype "unspecified"))
      (node (ref "U6") (pin "1") (pinfunction "1OE#_1") (pintype "unspecified"))
      (node (ref "U6") (pin "10") (pinfunction "3OE#_10") (pintype "unspecified"))
      (node (ref "U6") (pin "13") (pinfunction "4OE#_13") (pintype "unspecified"))
      (node (ref "U6") (pin "4") (pinfunction "2OE#_4") (pintype "unspecified"))
      (node (ref "U6") (pin "7") (pinfunction "GND_7") (pintype "unspecified"))
      (node (ref "U7") (pin "1") (pinfunction "VSS_1") (pintype "unspecified"))
      (node (ref "U8") (pin "17") (pinfunction "GND/AGND/Vref-_17") (pintype "unspecified"))
      (node (ref "U9") (pin "1") (pinfunction "GND_1") (pintype "unspecified"))
    )
    (net (code "18") (name "GPIO65") (class "Default")
      (node (ref "CN13") (pin "6") (pinfunction "6_6") (pintype "unspecified"))
      (node (ref "R46") (pin "1") (pinfunction "1_1") (pintype "unspecified"))
      (node (ref "U6") (pin "5") (pinfunction "2A_5") (pintype "unspecified"))
    )
    (net (code "19") (name "GPIO66") (class "Default")
      (node (ref "CN13") (pin "1") (pinfunction "1_1") (pintype "unspecified"))
      (node (ref "R45") (pin "2") (pinfunction "2_2") (pintype "unspecified"))
      (node (ref "U6") (pin "9") (pinfunction "3A_9") (pintype "unspecified"))
    )
    (net (code "20") (name "GPIO72") (class "Default")
      (node (ref "CN13") (pin "3") (pinfunction "3_3") (pintype "unspecified"))
      (node (ref "R47") (pin "2") (pinfunction "2_2") (pintype "unspecified"))
      (node (ref "U6") (pin "12") (pinfunction "4A_12") (pintype "unspecified"))
    )
    (net (code "21") (name "GPIO73") (class "Default")
      (node (ref "CN13") (pin "4") (pinfunction "4_4") (pintype "unspecified"))
      (node (ref "R44") (pin "1") (pinfunction "1_1") (pintype "unspecified"))
      (node (ref "U6") (pin "2") (pinfunction "1A_2") (pintype "unspecified"))
    )
    (net (code "22") (name "HOA1") (class "Default")
      (node (ref "R67") (pin "1") (pinfunction "1_1") (pintype "unspecified"))
      (node (ref "U10") (pin "19") (pinfunction "HO1_19") (pintype "unspecified"))
    )
    (net (code "23") (name "HOA2") (class "Default")
      (node (ref "R86") (pin "1") (pinfunction "1_1") (pintype "unspecified"))
      (node (ref "U19") (pin "19") (pinfunction "HO1_19") (pintype "unspecified"))
    )
    (net (code "24") (name "HOB1") (class "Default")
      (node (ref "R69") (pin "1") (pinfunction "1_1") (pintype "unspecified"))
      (node (ref "U10") (pin "16") (pinfunction "HO2_16") (pintype "unspecified"))
    )
    (net (code "25") (name "HOB2") (class "Default")
      (node (ref "R88") (pin "1") (pinfunction "1_1") (pintype "unspecified"))
      (node (ref "U19") (pin "16") (pinfunction "HO2_16") (pintype "unspecified"))
    )
    (net (code "26") (name "HOC1") (class "Default")
      (node (ref "R71") (pin "1") (pinfunction "1_1") (pintype "unspecified"))
      (node (ref "U10") (pin "13") (pinfunction "HO3_13") (pintype "unspecified"))
    )
    (net (code "27") (name "HOC2") (class "Default")
      (node (ref "R90") (pin "1") (pinfunction "1_1") (pintype "unspecified"))
      (node (ref "U19") (pin "13") (pinfunction "HO3_13") (pintype "unspecified"))
    )
    (net (code "28") (name "LED1") (class "Default")
      (node (ref "R52") (pin "1") (pinfunction "1_1") (pintype "unspecified"))
      (node (ref "U8") (pin "32") (pinfunction "TXD_4/RD/P4.4_32") (pintype "unspecified"))
    )
    (net (code "29") (name "LED2") (class "Default")
      (node (ref "R75") (pin "1") (pinfunction "1_1") (pintype "unspecified"))
      (node (ref "U17") (pin "32") (pinfunction "TXD_4/RD/P4.4_32") (pintype "unspecified"))
    )
    (net (code "30") (name "LOA1") (class "Default")
      (node (ref "R68") (pin "1") (pinfunction "1_1") (pintype "unspecified"))
      (node (ref "U10") (pin "11") (pinfunction "LO1_11") (pintype "unspecified"))
    )
    (net (code "31") (name "LOA2") (class "Default")
      (node (ref "R87") (pin "1") (pinfunction "1_1") (pintype "unspecified"))
      (node (ref "U19") (pin "11") (pinfunction "LO1_11") (pintype "unspecified"))
    )
    (net (code "32") (name "LOB1") (class "Default")
      (node (ref "R70") (pin "1") (pinfunction "1_1") (pintype "unspecified"))
      (node (ref "U10") (pin "10") (pinfunction "LO2_10") (pintype "unspecified"))
    )
    (net (code "33") (name "LOB2") (class "Default")
      (node (ref "R89") (pin "1") (pinfunction "1_1") (pintype "unspecified"))
      (node (ref "U19") (pin "10") (pinfunction "LO2_10") (pintype "unspecified"))
    )
    (net (code "34") (name "LOC1") (class "Default")
      (node (ref "R72") (pin "1") (pinfunction "1_1") (pintype "unspecified"))
      (node (ref "U10") (pin "9") (pinfunction "LO3_9") (pintype "unspecified"))
    )
    (net (code "35") (name "LOC2") (class "Default")
      (node (ref "R91") (pin "1") (pinfunction "1_1") (pintype "unspecified"))
      (node (ref "U19") (pin "9") (pinfunction "LO3_9") (pintype "unspecified"))
    )
    (net (code "36") (name "MID1") (class "Default")
      (node (ref "R56") (pin "2") (pinfunction "2_2") (pintype "input"))
      (node (ref "R61") (pin "2") (pinfunction "2_2") (pintype "input"))
      (node (ref "R64") (pin "2") (pinfunction "2_2") (pintype "input"))
      (node (ref "U8") (pin "27") (pinfunction "CMP-/RXD_2/INT2/P3.6_27") (pintype "unspecified"))
    )
    (net (code "37") (name "MID2") (class "Default")
      (node (ref "R77") (pin "2") (pinfunction "2_2") (pintype "input"))
      (node (ref "R80") (pin "2") (pinfunction "2_2") (pintype "input"))
      (node (ref "R83") (pin "2") (pinfunction "2_2") (pintype "input"))
      (node (ref "U17") (pin "27") (pinfunction "CMP-/RXD_2/INT2/P3.6_27") (pintype "unspecified"))
    )
    (net (code "38") (name "MOTOR1-A") (class "Default")
      (node (ref "CN8") (pin "1") (pinfunction "-_1") (pintype "unspecified"))
      (node (ref "Q3") (pin "1") (pinfunction "S_1") (pintype "unspecified"))
      (node (ref "Q3") (pin "2") (pinfunction "S_2") (pintype "unspecified"))
      (node (ref "Q3") (pin "3") (pinfunction "S_3") (pintype "unspecified"))
      (node (ref "Q5") (pin "5") (pinfunction "D_5") (pintype "unspecified"))
      (node (ref "Q5") (pin "6") (pinfunction "D_6") (pintype "unspecified"))
      (node (ref "Q5") (pin "7") (pinfunction "D_7") (pintype "unspecified"))
      (node (ref "Q5") (pin "8") (pinfunction "D_8") (pintype "unspecified"))
      (node (ref "Q5") (pin "9") (pinfunction "D_9") (pintype "unspecified"))
      (node (ref "U4") (pin "23") (pinfunction "SH2_23") (pintype "unspecified"))
    )
    (net (code "39") (name "MOTOR1-B") (class "Default")
      (node (ref "CN8") (pin "2") (pinfunction "+_2") (pintype "unspecified"))
      (node (ref "Q4") (pin "1") (pinfunction "S_1") (pintype "unspecified"))
      (node (ref "Q4") (pin "2") (pinfunction "S_2") (pintype "unspecified"))
      (node (ref "Q4") (pin "3") (pinfunction "S_3") (pintype "unspecified"))
      (node (ref "Q6") (pin "5") (pinfunction "D_5") (pintype "unspecified"))
      (node (ref "Q6") (pin "6") (pinfunction "D_6") (pintype "unspecified"))
      (node (ref "Q6") (pin "7") (pinfunction "D_7") (pintype "unspecified"))
      (node (ref "Q6") (pin "8") (pinfunction "D_8") (pintype "unspecified"))
      (node (ref "Q6") (pin "9") (pinfunction "D_9") (pintype "unspecified"))
      (node (ref "U4") (pin "18") (pinfunction "SH1_18") (pintype "unspecified"))
    )
    (net (code "40") (name "MOTOR2-A") (class "Default")
      (node (ref "CN7") (pin "1") (pinfunction "-_1") (pintype "unspecified"))
      (node (ref "Q7") (pin "1") (pinfunction "S_1") (pintype "unspecified"))
      (node (ref "Q7") (pin "2") (pinfunction "S_2") (pintype "unspecified"))
      (node (ref "Q7") (pin "3") (pinfunction "S_3") (pintype "unspecified"))
      (node (ref "Q9") (pin "5") (pinfunction "D_5") (pintype "unspecified"))
      (node (ref "Q9") (pin "6") (pinfunction "D_6") (pintype "unspecified"))
      (node (ref "Q9") (pin "7") (pinfunction "D_7") (pintype "unspecified"))
      (node (ref "Q9") (pin "8") (pinfunction "D_8") (pintype "unspecified"))
      (node (ref "Q9") (pin "9") (pinfunction "D_9") (pintype "unspecified"))
      (node (ref "U5") (pin "23") (pinfunction "SH2_23") (pintype "unspecified"))
    )
    (net (code "41") (name "MOTOR2-B") (class "Default")
      (node (ref "CN7") (pin "2") (pinfunction "+_2") (pintype "unspecified"))
      (node (ref "Q10") (pin "5") (pinfunction "D_5") (pintype "unspecified"))
      (node (ref "Q10") (pin "6") (pinfunction "D_6") (pintype "unspecified"))
      (node (ref "Q10") (pin "7") (pinfunction "D_7") (pintype "unspecified"))
      (node (ref "Q10") (pin "8") (pinfunction "D_8") (pintype "unspecified"))
      (node (ref "Q10") (pin "9") (pinfunction "D_9") (pintype "unspecified"))
      (node (ref "Q8") (pin "1") (pinfunction "S_1") (pintype "unspecified"))
      (node (ref "Q8") (pin "2") (pinfunction "S_2") (pintype "unspecified"))
      (node (ref "Q8") (pin "3") (pinfunction "S_3") (pintype "unspecified"))
      (node (ref "U5") (pin "18") (pinfunction "SH1_18") (pintype "unspecified"))
    )
    (net (code "42") (name "NSLEEP") (class "Default")
      (node (ref "R49") (pin "2") (pinfunction "2_2") (pintype "input"))
      (node (ref "SW2") (pin "3") (pinfunction "3_3") (pintype "unspecified"))
      (node (ref "U4") (pin "13") (pinfunction "nSLEEP_13") (pintype "unspecified"))
      (node (ref "U5") (pin "13") (pinfunction "nSLEEP_13") (pintype "unspecified"))
    )
    (net (code "43") (name "Net-(D4-K)") (class "Default")
      (node (ref "C18") (pin "2") (pinfunction "2_2") (pintype "unspecified"))
      (node (ref "C19") (pin "2") (pinfunction "2_2") (pintype "unspecified"))
      (node (ref "C20") (pin "2") (pinfunction "2_2") (pintype "unspecified"))
      (node (ref "D4") (pin "1") (pinfunction "K_1") (pintype "unspecified"))
      (node (ref "U4") (pin "1") (pinfunction "VM_1") (pintype "unspecified"))
    )
    (net (code "44") (name "Net-(D5-K)") (class "Default")
      (node (ref "C23") (pin "2") (pinfunction "2_2") (pintype "unspecified"))
      (node (ref "C24") (pin "2") (pinfunction "2_2") (pintype "unspecified"))
      (node (ref "C25") (pin "2") (pinfunction "2_2") (pintype "unspecified"))
      (node (ref "D5") (pin "1") (pinfunction "K_1") (pintype "unspecified"))
      (node (ref "U5") (pin "1") (pinfunction "VM_1") (pintype "unspecified"))
    )
    (net (code "45") (name "Net-(D8-K)") (class "Default")
      (node (ref "C52") (pin "2") (pinfunction "2_2") (pintype "unspecified"))
      (node (ref "D8") (pin "1") (pinfunction "K_1") (pintype "unspecified"))
      (node (ref "U9") (pin "2") (pinfunction "VIN_2") (pintype "unspecified"))
    )
    (net (code "46") (name "Net-(D10-A)") (class "Default")
      (node (ref "C55") (pin "1") (pinfunction "1_1") (pintype "unspecified"))
      (node (ref "D10") (pin "1") (pinfunction "A_1") (pintype "unspecified"))
      (node (ref "D11") (pin "1") (pinfunction "A_1") (pintype "unspecified"))
      (node (ref "D12") (pin "1") (pinfunction "K_1") (pintype "unspecified"))
      (node (ref "D9") (pin "1") (pinfunction "A_1") (pintype "unspecified"))
      (node (ref "R66") (pin "2") (pinfunction "2_2") (pintype "input"))
      (node (ref "U10") (pin "4") (pinfunction "VCC_4") (pintype "unspecified"))
    )
    (net (code "47") (name "Net-(D16-A)") (class "Default")
      (node (ref "C77") (pin "1") (pinfunction "1_1") (pintype "unspecified"))
      (node (ref "D16") (pin "1") (pinfunction "A_1") (pintype "unspecified"))
      (node (ref "D17") (pin "1") (pinfunction "A_1") (pintype "unspecified"))
      (node (ref "D18") (pin "1") (pinfunction "A_1") (pintype "unspecified"))
      (node (ref "D19") (pin "1") (pinfunction "K_1") (pintype "unspecified"))
      (node (ref "R85") (pin "2") (pinfunction "2_2") (pintype "input"))
      (node (ref "U19") (pin "4") (pinfunction "VCC_4") (pintype "unspecified"))
    )
    (net (code "48") (name "Net-(LED4-A)") (class "Default")
      (node (ref "LED4") (pin "2") (pinfunction "A_2") (pintype "input"))
      (node (ref "R48") (pin "1") (pinfunction "1_1") (pintype "input"))
    )
    (net (code "49") (name "Net-(LED5-+)") (class "Default")
      (node (ref "LED5") (pin "2") (pinfunction "+_2") (pintype "input"))
      (node (ref "R49") (pin "1") (pinfunction "1_1") (pintype "input"))
    )
    (net (code "50") (name "Net-(LED6-K)") (class "Default")
      (node (ref "LED6") (pin "1") (pinfunction "K_1") (pintype "input"))
      (node (ref "R52") (pin "2") (pinfunction "2_2") (pintype "unspecified"))
    )
    (net (code "51") (name "Net-(LED7-K)") (class "Default")
      (node (ref "LED7") (pin "1") (pinfunction "K_1") (pintype "input"))
      (node (ref "R75") (pin "2") (pinfunction "2_2") (pintype "unspecified"))
    )
    (net (code "52") (name "Net-(Q3-G)") (class "Default")
      (node (ref "Q3") (pin "4") (pinfunction "G_4") (pintype "unspecified"))
      (node (ref "U4") (pin "24") (pinfunction "GH2_24") (pintype "unspecified"))
    )
    (net (code "53") (name "Net-(Q4-G)") (class "Default")
      (node (ref "Q4") (pin "4") (pinfunction "G_4") (pintype "unspecified"))
      (node (ref "U4") (pin "17") (pinfunction "GH1_17") (pintype "unspecified"))
    )
    (net (code "54") (name "Net-(Q5-G)") (class "Default")
      (node (ref "Q5") (pin "4") (pinfunction "G_4") (pintype "unspecified"))
      (node (ref "U4") (pin "22") (pinfunction "GL2_22") (pintype "unspecified"))
    )
    (net (code "55") (name "Net-(Q6-G)") (class "Default")
      (node (ref "Q6") (pin "4") (pinfunction "G_4") (pintype "unspecified"))
      (node (ref "U4") (pin "19") (pinfunction "GL1_19") (pintype "unspecified"))
    )
    (net (code "56") (name "Net-(Q7-G)") (class "Default")
      (node (ref "Q7") (pin "4") (pinfunction "G_4") (pintype "unspecified"))
      (node (ref "U5") (pin "24") (pinfunction "GH2_24") (pintype "unspecified"))
    )
    (net (code "57") (name "Net-(Q8-G)") (class "Default")
      (node (ref "Q8") (pin "4") (pinfunction "G_4") (pintype "unspecified"))
      (node (ref "U5") (pin "17") (pinfunction "GH1_17") (pintype "unspecified"))
    )
    (net (code "58") (name "Net-(Q9-G)") (class "Default")
      (node (ref "Q9") (pin "4") (pinfunction "G_4") (pintype "unspecified"))
      (node (ref "U5") (pin "22") (pinfunction "GL2_22") (pintype "unspecified"))
    )
    (net (code "59") (name "Net-(Q10-G)") (class "Default")
      (node (ref "Q10") (pin "4") (pinfunction "G_4") (pintype "unspecified"))
      (node (ref "U5") (pin "19") (pinfunction "GL1_19") (pintype "unspecified"))
    )
    (net (code "60") (name "Net-(Q12-G)") (class "Default")
      (node (ref "Q12") (pin "4") (pinfunction "G_4") (pintype "unspecified"))
      (node (ref "R71") (pin "2") (pinfunction "2_2") (pintype "unspecified"))
    )
    (net (code "61") (name "Net-(Q13-G)") (class "Default")
      (node (ref "Q13") (pin "4") (pinfunction "G_4") (pintype "unspecified"))
      (node (ref "R69") (pin "2") (pinfunction "2_2") (pintype "unspecified"))
    )
    (net (code "62") (name "Net-(Q14-G)") (class "Default")
      (node (ref "Q14") (pin "4") (pinfunction "G_4") (pintype "unspecified"))
      (node (ref "R67") (pin "2") (pinfunction "2_2") (pintype "unspecified"))
    )
    (net (code "63") (name "Net-(Q15-G)") (class "Default")
      (node (ref "Q15") (pin "4") (pinfunction "G_4") (pintype "unspecified"))
      (node (ref "R68") (pin "2") (pinfunction "2_2") (pintype "unspecified"))
    )
    (net (code "64") (name "Net-(Q16-G)") (class "Default")
      (node (ref "Q16") (pin "4") (pinfunction "G_4") (pintype "unspecified"))
      (node (ref "R70") (pin "2") (pinfunction "2_2") (pintype "unspecified"))
    )
    (net (code "65") (name "Net-(Q17-G)") (class "Default")
      (node (ref "Q17") (pin "4") (pinfunction "G_4") (pintype "unspecified"))
      (node (ref "R72") (pin "2") (pinfunction "2_2") (pintype "unspecified"))
    )
    (net (code "66") (name "Net-(Q18-G)") (class "Default")
      (node (ref "Q18") (pin "4") (pinfunction "G_4") (pintype "unspecified"))
      (node (ref "R86") (pin "2") (pinfunction "2_2") (pintype "unspecified"))
    )
    (net (code "67") (name "Net-(Q19-G)") (class "Default")
      (node (ref "Q19") (pin "4") (pinfunction "G_4") (pintype "unspecified"))
      (node (ref "R88") (pin "2") (pinfunction "2_2") (pintype "unspecified"))
    )
    (net (code "68") (name "Net-(Q20-G)") (class "Default")
      (node (ref "Q20") (pin "4") (pinfunction "G_4") (pintype "unspecified"))
      (node (ref "R90") (pin "2") (pinfunction "2_2") (pintype "unspecified"))
    )
    (net (code "69") (name "Net-(Q21-G)") (class "Default")
      (node (ref "Q21") (pin "4") (pinfunction "G_4") (pintype "unspecified"))
      (node (ref "R87") (pin "2") (pinfunction "2_2") (pintype "unspecified"))
    )
    (net (code "70") (name "Net-(Q22-G)") (class "Default")
      (node (ref "Q22") (pin "4") (pinfunction "G_4") (pintype "unspecified"))
      (node (ref "R89") (pin "2") (pinfunction "2_2") (pintype "unspecified"))
    )
    (net (code "71") (name "Net-(Q23-G)") (class "Default")
      (node (ref "Q23") (pin "4") (pinfunction "G_4") (pintype "unspecified"))
      (node (ref "R91") (pin "2") (pinfunction "2_2") (pintype "unspecified"))
    )
    (net (code "72") (name "Net-(U4-AVDD)") (class "Default")
      (node (ref "C22") (pin "2") (pinfunction "2_2") (pintype "unspecified"))
      (node (ref "U4") (pin "12") (pinfunction "IDRIVE_12") (pintype "unspecified"))
      (node (ref "U4") (pin "6") (pinfunction "VREF_6") (pintype "unspecified"))
      (node (ref "U4") (pin "7") (pinfunction "AVDD_7") (pintype "unspecified"))
    )
    (net (code "73") (name "Net-(U4-CPH)") (class "Default")
      (node (ref "C21") (pin "2") (pinfunction "2_2") (pintype "unspecified"))
      (node (ref "U4") (pin "3") (pinfunction "CPH_3") (pintype "unspecified"))
    )
    (net (code "74") (name "Net-(U4-CPL)") (class "Default")
      (node (ref "C21") (pin "1") (pinfunction "1_1") (pintype "unspecified"))
      (node (ref "U4") (pin "4") (pinfunction "CPL_4") (pintype "unspecified"))
    )
    (net (code "75") (name "Net-(U4-VCP)") (class "Default")
      (node (ref "C20") (pin "1") (pinfunction "1_1") (pintype "unspecified"))
      (node (ref "U4") (pin "2") (pinfunction "VCP_2") (pintype "unspecified"))
    )
    (net (code "76") (name "Net-(U5-AVDD)") (class "Default")
      (node (ref "C27") (pin "2") (pinfunction "2_2") (pintype "unspecified"))
      (node (ref "U5") (pin "12") (pinfunction "IDRIVE_12") (pintype "unspecified"))
      (node (ref "U5") (pin "6") (pinfunction "VREF_6") (pintype "unspecified"))
      (node (ref "U5") (pin "7") (pinfunction "AVDD_7") (pintype "unspecified"))
    )
    (net (code "77") (name "Net-(U5-CPH)") (class "Default")
      (node (ref "C26") (pin "2") (pinfunction "2_2") (pintype "unspecified"))
      (node (ref "U5") (pin "3") (pinfunction "CPH_3") (pintype "unspecified"))
    )
    (net (code "78") (name "Net-(U5-CPL)") (class "Default")
      (node (ref "C26") (pin "1") (pinfunction "1_1") (pintype "unspecified"))
      (node (ref "U5") (pin "4") (pinfunction "CPL_4") (pintype "unspecified"))
    )
    (net (code "79") (name "Net-(U5-VCP)") (class "Default")
      (node (ref "C25") (pin "1") (pinfunction "1_1") (pintype "unspecified"))
      (node (ref "U5") (pin "2") (pinfunction "VCP_2") (pintype "unspecified"))
    )
    (net (code "80") (name "Net-(U7-VOUT)") (class "Default")
      (node (ref "C30") (pin "2") (pinfunction "2_2") (pintype "unspecified"))
      (node (ref "R48") (pin "2") (pinfunction "2_2") (pintype "input"))
      (node (ref "SW2") (pin "2") (pinfunction "2_2") (pintype "unspecified"))
      (node (ref "U7") (pin "2") (pinfunction "VOUT_2") (pintype "unspecified"))
    )
    (net (code "81") (name "Net-(U8-UCAP)") (class "Default")
      (node (ref "C32") (pin "2") (pinfunction "2_2") (pintype "unspecified"))
      (node (ref "U8") (pin "13") (pinfunction "UCAP_13") (pintype "unspecified"))
    )
    (net (code "82") (name "Net-(U8-Vref)") (class "Default")
      (node (ref "C35") (pin "2") (pinfunction "2_2") (pintype "unspecified"))
      (node (ref "L1") (pin "1") (pinfunction "1_1") (pintype "unspecified"))
      (node (ref "U8") (pin "16") (pinfunction "Vref_16") (pintype "unspecified"))
    )
    (net (code "83") (name "Net-(U17-UCAP)") (class "Default")
      (node (ref "C59") (pin "2") (pinfunction "2_2") (pintype "unspecified"))
      (node (ref "U17") (pin "13") (pinfunction "UCAP_13") (pintype "unspecified"))
    )
    (net (code "84") (name "Net-(U17-Vref)") (class "Default")
      (node (ref "C62") (pin "2") (pinfunction "2_2") (pintype "unspecified"))
      (node (ref "L2") (pin "1") (pinfunction "1_1") (pintype "unspecified"))
      (node (ref "U17") (pin "16") (pinfunction "Vref_16") (pintype "unspecified"))
    )
    (net (code "85") (name "PH_1") (class "Default")
      (node (ref "U4") (pin "15") (pinfunction "PH_15") (pintype "unspecified"))
      (node (ref "U6") (pin "3") (pinfunction "1Y_3") (pintype "unspecified"))
    )
    (net (code "86") (name "PH_2") (class "Default")
      (node (ref "U5") (pin "15") (pinfunction "PH_15") (pintype "unspecified"))
      (node (ref "U6") (pin "11") (pinfunction "4Y_11") (pintype "unspecified"))
    )
    (net (code "87") (name "PWMAH1") (class "Default")
      (node (ref "U10") (pin "22") (pinfunction "HIN1_22") (pintype "unspecified"))
      (node (ref "U8") (pin "33") (pinfunction "PWM5/PWM1P_2/A8/P2.0_33") (pintype "unspecified"))
    )
    (net (code "88") (name "PWMAH2") (class "Default")
      (node (ref "U17") (pin "33") (pinfunction "PWM5/PWM1P_2/A8/P2.0_33") (pintype "unspecified"))
      (node (ref "U19") (pin "22") (pinfunction "HIN1_22") (pintype "unspecified"))
    )
    (net (code "89") (name "PWMAL1") (class "Default")
      (node (ref "U10") (pin "1") (pinfunction "LIN1_1") (pintype "unspecified"))
      (node (ref "U8") (pin "34") (pinfunction "PWM6/PWM1N_2/A9/P2.1_34") (pintype "unspecified"))
    )
    (net (code "90") (name "PWMAL2") (class "Default")
      (node (ref "U17") (pin "34") (pinfunction "PWM6/PWM1N_2/A9/P2.1_34") (pintype "unspecified"))
      (node (ref "U19") (pin "1") (pinfunction "LIN1_1") (pintype "unspecified"))
    )
    (net (code "91") (name "PWMBH1") (class "Default")
      (node (ref "U10") (pin "23") (pinfunction "HIN2_23") (pintype "unspecified"))
      (node (ref "U8") (pin "35") (pinfunction "PWM7/PWM2P_2/S2SS_2/S1SS_2/SS_2/A10/P2.2_35") (pintype "unspecified"))
    )
    (net (code "92") (name "PWMBH2") (class "Default")
      (node (ref "U17") (pin "35") (pinfunction "PWM7/PWM2P_2/S2SS_2/S1SS_2/SS_2/A10/P2.2_35") (pintype "unspecified"))
      (node (ref "U19") (pin "23") (pinfunction "HIN2_23") (pintype "unspecified"))
    )
    (net (code "93") (name "PWMBL1") (class "Default")
      (node (ref "U10") (pin "2") (pinfunction "LIN2_2") (pintype "unspecified"))
      (node (ref "U8") (pin "36") (pinfunction "PWM8/PWM2N_2/S2MOSI_2/S1MOSI_2/MOSI_2/A11/P2.3_36") (pintype "unspecified"))
    )
    (net (code "94") (name "PWMBL2") (class "Default")
      (node (ref "U17") (pin "36") (pinfunction "PWM8/PWM2N_2/S2MOSI_2/S1MOSI_2/MOSI_2/A11/P2.3_36") (pintype "unspecified"))
      (node (ref "U19") (pin "2") (pinfunction "LIN2_2") (pintype "unspecified"))
    )
    (net (code "95") (name "PWMCH1") (class "Default")
      (node (ref "U10") (pin "24") (pinfunction "HIN3_24") (pintype "unspecified"))
      (node (ref "U8") (pin "37") (pinfunction "PWM3P_2/SDA_2/S2MISO_2/S1MISO_2/MISO_2/A12/P2.4_37") (pintype "unspecified"))
    )
    (net (code "96") (name "PWMCH2") (class "Default")
      (node (ref "U17") (pin "37") (pinfunction "PWM3P_2/SDA_2/S2MISO_2/S1MISO_2/MISO_2/A12/P2.4_37") (pintype "unspecified"))
      (node (ref "U19") (pin "24") (pinfunction "HIN3_24") (pintype "unspecified"))
    )
    (net (code "97") (name "PWMCL1") (class "Default")
      (node (ref "U10") (pin "3") (pinfunction "LIN3_3") (pintype "unspecified"))
      (node (ref "U8") (pin "38") (pinfunction "PWM3N_2/SCL_2/S2SCLK_2/S1SCLK_2/SCLK_2/A13/P2.5_38") (pintype "unspecified"))
    )
    (net (code "98") (name "PWMCL2") (class "Default")
      (node (ref "U17") (pin "38") (pinfunction "PWM3N_2/SCL_2/S2SCLK_2/S1SCLK_2/SCLK_2/A13/P2.5_38") (pintype "unspecified"))
      (node (ref "U19") (pin "3") (pinfunction "LIN3_3") (pintype "unspecified"))
    )
    (net (code "99") (name "PWMIN1") (class "Default")
      (node (ref "CN11") (pin "6") (pinfunction "6_6") (pintype "unspecified"))
      (node (ref "U8") (pin "43") (pinfunction "CAN_RX/PWM5_3/RXD3/ADC8/AD0/P0.0_43") (pintype "unspecified"))
      (node (ref "U8") (pin "44") (pinfunction "CAN_TX/PWM6_3/TXD3/ADC9/AD1/P0.1_44") (pintype "unspecified"))
    )
    (net (code "100") (name "PWMIN2") (class "Default")
      (node (ref "CN11") (pin "1") (pinfunction "1_1") (pintype "unspecified"))
      (node (ref "U17") (pin "43") (pinfunction "CAN_RX/PWM5_3/RXD3/ADC8/AD0/P0.0_43") (pintype "unspecified"))
      (node (ref "U17") (pin "44") (pinfunction "CAN_TX/PWM6_3/TXD3/ADC9/AD1/P0.1_44") (pintype "unspecified"))
    )
    (net (code "101") (name "VBA1") (class "Default")
      (node (ref "C56") (pin "1") (pinfunction "1_1") (pintype "input"))
      (node (ref "D9") (pin "2") (pinfunction "K_2") (pintype "unspecified"))
      (node (ref "U10") (pin "20") (pinfunction "VB1_20") (pintype "unspecified"))
    )
    (net (code "102") (name "VBA2") (class "Default")
      (node (ref "C78") (pin "1") (pinfunction "1_1") (pintype "input"))
      (node (ref "D16") (pin "2") (pinfunction "K_2") (pintype "unspecified"))
      (node (ref "U19") (pin "20") (pinfunction "VB1_20") (pintype "unspecified"))
    )
    (net (code "103") (name "VBB1") (class "Default")
      (node (ref "C57") (pin "1") (pinfunction "1_1") (pintype "input"))
      (node (ref "D10") (pin "2") (pinfunction "K_2") (pintype "unspecified"))
      (node (ref "U10") (pin "17") (pinfunction "VB2_17") (pintype "unspecified"))
    )
    (net (code "104") (name "VBB2") (class "Default")
      (node (ref "C79") (pin "1") (pinfunction "1_1") (pintype "input"))
      (node (ref "D17") (pin "2") (pinfunction "K_2") (pintype "unspecified"))
      (node (ref "U19") (pin "17") (pinfunction "VB2_17") (pintype "unspecified"))
    )
    (net (code "105") (name "VBC1") (class "Default")
      (node (ref "C58") (pin "1") (pinfunction "1_1") (pintype "input"))
      (node (ref "D11") (pin "2") (pinfunction "K_2") (pintype "unspecified"))
      (node (ref "U10") (pin "14") (pinfunction "VB3_14") (pintype "unspecified"))
    )
    (net (code "106") (name "VBC2") (class "Default")
      (node (ref "C80") (pin "1") (pinfunction "1_1") (pintype "input"))
      (node (ref "D18") (pin "2") (pinfunction "K_2") (pintype "unspecified"))
      (node (ref "U19") (pin "14") (pinfunction "VB3_14") (pintype "unspecified"))
    )
    (net (code "107") (name "VCCBAT") (class "Default")
      (node (ref "C29") (pin "2") (pinfunction "2_2") (pintype "unspecified"))
      (node (ref "C31") (pin "1") (pinfunction "1_1") (pintype "input"))
      (node (ref "C40") (pin "2") (pinfunction "2_2") (pintype "unspecified"))
      (node (ref "C46") (pin "1") (pinfunction "1_1") (pintype "input"))
      (node (ref "C47") (pin "2") (pinfunction "2_2") (pintype "unspecified"))
      (node (ref "C48") (pin "2") (pinfunction "2_2") (pintype "unspecified"))
      (node (ref "C49") (pin "2") (pinfunction "2_2") (pintype "unspecified"))
      (node (ref "C50") (pin "2") (pinfunction "2_2") (pintype "unspecified"))
      (node (ref "C51") (pin "2") (pinfunction "2_2") (pintype "unspecified"))
      (node (ref "CN9") (pin "2") (pinfunction "+_2") (pintype "unspecified"))
      (node (ref "D4") (pin "2") (pinfunction "A_2") (pintype "unspecified"))
      (node (ref "D5") (pin "2") (pinfunction "A_2") (pintype "unspecified"))
      (node (ref "D8") (pin "2") (pinfunction "A_2") (pintype "unspecified"))
      (node (ref "Q12") (pin "5") (pinfunction "D_5") (pintype "unspecified"))
      (node (ref "Q12") (pin "6") (pinfunction "D_6") (pintype "unspecified"))
      (node (ref "Q12") (pin "7") (pinfunction "D_7") (pintype "unspecified"))
      (node (ref "Q12") (pin "8") (pinfunction "D_8") (pintype "unspecified"))
      (node (ref "Q12") (pin "9") (pinfunction "D_9") (pintype "unspecified"))
      (node (ref "Q13") (pin "5") (pinfunction "D_5") (pintype "unspecified"))
      (node (ref "Q13") (pin "6") (pinfunction "D_6") (pintype "unspecified"))
      (node (ref "Q13") (pin "7") (pinfunction "D_7") (pintype "unspecified"))
      (node (ref "Q13") (pin "8") (pinfunction "D_8") (pintype "unspecified"))
      (node (ref "Q13") (pin "9") (pinfunction "D_9") (pintype "unspecified"))
      (node (ref "Q14") (pin "5") (pinfunction "D_5") (pintype "unspecified"))
      (node (ref "Q14") (pin "6") (pinfunction "D_6") (pintype "unspecified"))
      (node (ref "Q14") (pin "7") (pinfunction "D_7") (pintype "unspecified"))
      (node (ref "Q14") (pin "8") (pinfunction "D_8") (pintype "unspecified"))
      (node (ref "Q14") (pin "9") (pinfunction "D_9") (pintype "unspecified"))
      (node (ref "Q18") (pin "5") (pinfunction "D_5") (pintype "unspecified"))
      (node (ref "Q18") (pin "6") (pinfunction "D_6") (pintype "unspecified"))
      (node (ref "Q18") (pin "7") (pinfunction "D_7") (pintype "unspecified"))
      (node (ref "Q18") (pin "8") (pinfunction "D_8") (pintype "unspecified"))
      (node (ref "Q18") (pin "9") (pinfunction "D_9") (pintype "unspecified"))
      (node (ref "Q19") (pin "5") (pinfunction "D_5") (pintype "unspecified"))
      (node (ref "Q19") (pin "6") (pinfunction "D_6") (pintype "unspecified"))
      (node (ref "Q19") (pin "7") (pinfunction "D_7") (pintype "unspecified"))
      (node (ref "Q19") (pin "8") (pinfunction "D_8") (pintype "unspecified"))
      (node (ref "Q19") (pin "9") (pinfunction "D_9") (pintype "unspecified"))
      (node (ref "Q20") (pin "5") (pinfunction "D_5") (pintype "unspecified"))
      (node (ref "Q20") (pin "6") (pinfunction "D_6") (pintype "unspecified"))
      (node (ref "Q20") (pin "7") (pinfunction "D_7") (pintype "unspecified"))
      (node (ref "Q20") (pin "8") (pinfunction "D_8") (pintype "unspecified"))
      (node (ref "Q20") (pin "9") (pinfunction "D_9") (pintype "unspecified"))
      (node (ref "Q3") (pin "5") (pinfunction "D_5") (pintype "unspecified"))
      (node (ref "Q3") (pin "6") (pinfunction "D_6") (pintype "unspecified"))
      (node (ref "Q3") (pin "7") (pinfunction "D_7") (pintype "unspecified"))
      (node (ref "Q3") (pin "8") (pinfunction "D_8") (pintype "unspecified"))
      (node (ref "Q3") (pin "9") (pinfunction "D_9") (pintype "unspecified"))
      (node (ref "Q4") (pin "5") (pinfunction "D_5") (pintype "unspecified"))
      (node (ref "Q4") (pin "6") (pinfunction "D_6") (pintype "unspecified"))
      (node (ref "Q4") (pin "7") (pinfunction "D_7") (pintype "unspecified"))
      (node (ref "Q4") (pin "8") (pinfunction "D_8") (pintype "unspecified"))
      (node (ref "Q4") (pin "9") (pinfunction "D_9") (pintype "unspecified"))
      (node (ref "Q7") (pin "5") (pinfunction "D_5") (pintype "unspecified"))
      (node (ref "Q7") (pin "6") (pinfunction "D_6") (pintype "unspecified"))
      (node (ref "Q7") (pin "7") (pinfunction "D_7") (pintype "unspecified"))
      (node (ref "Q7") (pin "8") (pinfunction "D_8") (pintype "unspecified"))
      (node (ref "Q7") (pin "9") (pinfunction "D_9") (pintype "unspecified"))
      (node (ref "Q8") (pin "5") (pinfunction "D_5") (pintype "unspecified"))
      (node (ref "Q8") (pin "6") (pinfunction "D_6") (pintype "unspecified"))
      (node (ref "Q8") (pin "7") (pinfunction "D_7") (pintype "unspecified"))
      (node (ref "Q8") (pin "8") (pinfunction "D_8") (pintype "unspecified"))
      (node (ref "Q8") (pin "9") (pinfunction "D_9") (pintype "unspecified"))
      (node (ref "R50") (pin "2") (pinfunction "2_2") (pintype "input"))
      (node (ref "R66") (pin "1") (pinfunction "1_1") (pintype "input"))
      (node (ref "R73") (pin "2") (pinfunction "2_2") (pintype "input"))
      (node (ref "R85") (pin "1") (pinfunction "1_1") (pintype "input"))
      (node (ref "U7") (pin "3") (pinfunction "VIN_3") (pintype "unspecified"))
    )
    (net (code "108") (name "VSA1") (class "Default")
      (node (ref "C56") (pin "2") (pinfunction "2_2") (pintype "input"))
      (node (ref "Q14") (pin "1") (pinfunction "S_1") (pintype "unspecified"))
      (node (ref "Q14") (pin "2") (pinfunction "S_2") (pintype "unspecified"))
      (node (ref "Q14") (pin "3") (pinfunction "S_3") (pintype "unspecified"))
      (node (ref "Q15") (pin "5") (pinfunction "D_5") (pintype "unspecified"))
      (node (ref "Q15") (pin "6") (pinfunction "D_6") (pintype "unspecified"))
      (node (ref "Q15") (pin "7") (pinfunction "D_7") (pintype "unspecified"))
      (node (ref "Q15") (pin "8") (pinfunction "D_8") (pintype "unspecified"))
      (node (ref "Q15") (pin "9") (pinfunction "D_9") (pintype "unspecified"))
      (node (ref "R53") (pin "2") (pinfunction "2_2") (pintype "input"))
      (node (ref "TP1") (pin "1") (pinfunction "1_1") (pintype "input"))
      (node (ref "U10") (pin "18") (pinfunction "VS1_18") (pintype "unspecified"))
    )
    (net (code "109") (name "VSA2") (class "Default")
      (node (ref "C78") (pin "2") (pinfunction "2_2") (pintype "input"))
      (node (ref "Q18") (pin "1") (pinfunction "S_1") (pintype "unspecified"))
      (node (ref "Q18") (pin "2") (pinfunction "S_2") (pintype "unspecified"))
      (node (ref "Q18") (pin "3") (pinfunction "S_3") (pintype "unspecified"))
      (node (ref "Q21") (pin "5") (pinfunction "D_5") (pintype "unspecified"))
      (node (ref "Q21") (pin "6") (pinfunction "D_6") (pintype "unspecified"))
      (node (ref "Q21") (pin "7") (pinfunction "D_7") (pintype "unspecified"))
      (node (ref "Q21") (pin "8") (pinfunction "D_8") (pintype "unspecified"))
      (node (ref "Q21") (pin "9") (pinfunction "D_9") (pintype "unspecified"))
      (node (ref "R76") (pin "2") (pinfunction "2_2") (pintype "input"))
      (node (ref "TP4") (pin "1") (pinfunction "1_1") (pintype "input"))
      (node (ref "U19") (pin "18") (pinfunction "VS1_18") (pintype "unspecified"))
    )
    (net (code "110") (name "VSB1") (class "Default")
      (node (ref "C57") (pin "2") (pinfunction "2_2") (pintype "input"))
      (node (ref "Q13") (pin "1") (pinfunction "S_1") (pintype "unspecified"))
      (node (ref "Q13") (pin "2") (pinfunction "S_2") (pintype "unspecified"))
      (node (ref "Q13") (pin "3") (pinfunction "S_3") (pintype "unspecified"))
      (node (ref "Q16") (pin "5") (pinfunction "D_5") (pintype "unspecified"))
      (node (ref "Q16") (pin "6") (pinfunction "D_6") (pintype "unspecified"))
      (node (ref "Q16") (pin "7") (pinfunction "D_7") (pintype "unspecified"))
      (node (ref "Q16") (pin "8") (pinfunction "D_8") (pintype "unspecified"))
      (node (ref "Q16") (pin "9") (pinfunction "D_9") (pintype "unspecified"))
      (node (ref "R60") (pin "2") (pinfunction "2_2") (pintype "input"))
      (node (ref "TP2") (pin "1") (pinfunction "1_1") (pintype "input"))
      (node (ref "U10") (pin "15") (pinfunction "VS2_15") (pintype "unspecified"))
    )
    (net (code "111") (name "VSB2") (class "Default")
      (node (ref "C79") (pin "2") (pinfunction "2_2") (pintype "input"))
      (node (ref "Q19") (pin "1") (pinfunction "S_1") (pintype "unspecified"))
      (node (ref "Q19") (pin "2") (pinfunction "S_2") (pintype "unspecified"))
      (node (ref "Q19") (pin "3") (pinfunction "S_3") (pintype "unspecified"))
      (node (ref "Q22") (pin "5") (pinfunction "D_5") (pintype "unspecified"))
      (node (ref "Q22") (pin "6") (pinfunction "D_6") (pintype "unspecified"))
      (node (ref "Q22") (pin "7") (pinfunction "D_7") (pintype "unspecified"))
      (node (ref "Q22") (pin "8") (pinfunction "D_8") (pintype "unspecified"))
      (node (ref "Q22") (pin "9") (pinfunction "D_9") (pintype "unspecified"))
      (node (ref "R79") (pin "2") (pinfunction "2_2") (pintype "input"))
      (node (ref "TP5") (pin "1") (pinfunction "1_1") (pintype "input"))
      (node (ref "U19") (pin "15") (pinfunction "VS2_15") (pintype "unspecified"))
    )
    (net (code "112") (name "VSC1") (class "Default")
      (node (ref "C58") (pin "2") (pinfunction "2_2") (pintype "input"))
      (node (ref "Q12") (pin "1") (pinfunction "S_1") (pintype "unspecified"))
      (node (ref "Q12") (pin "2") (pinfunction "S_2") (pintype "unspecified"))
      (node (ref "Q12") (pin "3") (pinfunction "S_3") (pintype "unspecified"))
      (node (ref "Q17") (pin "5") (pinfunction "D_5") (pintype "unspecified"))
      (node (ref "Q17") (pin "6") (pinfunction "D_6") (pintype "unspecified"))
      (node (ref "Q17") (pin "7") (pinfunction "D_7") (pintype "unspecified"))
      (node (ref "Q17") (pin "8") (pinfunction "D_8") (pintype "unspecified"))
      (node (ref "Q17") (pin "9") (pinfunction "D_9") (pintype "unspecified"))
      (node (ref "R63") (pin "2") (pinfunction "2_2") (pintype "input"))
      (node (ref "TP3") (pin "1") (pinfunction "1_1") (pintype "input"))
      (node (ref "U10") (pin "12") (pinfunction "VS3_12") (pintype "unspecified"))
    )
    (net (code "113") (name "VSC2") (class "Default")
      (node (ref "C80") (pin "2") (pinfunction "2_2") (pintype "input"))
      (node (ref "Q20") (pin "1") (pinfunction "S_1") (pintype "unspecified"))
      (node (ref "Q20") (pin "2") (pinfunction "S_2") (pintype "unspecified"))
      (node (ref "Q20") (pin "3") (pinfunction "S_3") (pintype "unspecified"))
      (node (ref "Q23") (pin "5") (pinfunction "D_5") (pintype "unspecified"))
      (node (ref "Q23") (pin "6") (pinfunction "D_6") (pintype "unspecified"))
      (node (ref "Q23") (pin "7") (pinfunction "D_7") (pintype "unspecified"))
      (node (ref "Q23") (pin "8") (pinfunction "D_8") (pintype "unspecified"))
      (node (ref "Q23") (pin "9") (pinfunction "D_9") (pintype "unspecified"))
      (node (ref "R82") (pin "2") (pinfunction "2_2") (pintype "input"))
      (node (ref "TP6") (pin "1") (pinfunction "1_1") (pintype "input"))
      (node (ref "U19") (pin "12") (pinfunction "VS3_12") (pintype "unspecified"))
    )
    (net (code "114") (name "unconnected-(CN11-Pad2)") (class "Default")
      (node (ref "CN11") (pin "2") (pinfunction "2_2") (pintype "unspecified+no_connect"))
    )
    (net (code "115") (name "unconnected-(CN11-Pad5)") (class "Default")
      (node (ref "CN11") (pin "5") (pinfunction "5_5") (pintype "unspecified+no_connect"))
    )
    (net (code "116") (name "unconnected-(SW2-Pad1)") (class "Default")
      (node (ref "SW2") (pin "1") (pinfunction "1_1") (pintype "unspecified+no_connect"))
    )
    (net (code "117") (name "unconnected-(U4-SNSOUT-Pad10)") (class "Default")
      (node (ref "U4") (pin "10") (pinfunction "SNSOUT_10") (pintype "unspecified+no_connect"))
    )
    (net (code "118") (name "unconnected-(U4-SO-Pad11)") (class "Default")
      (node (ref "U4") (pin "11") (pinfunction "SO_11") (pintype "unspecified+no_connect"))
    )
    (net (code "119") (name "unconnected-(U4-nFAULT-Pad9)") (class "Default")
      (node (ref "U4") (pin "9") (pinfunction "nFAULT_9") (pintype "unspecified+no_connect"))
    )
    (net (code "120") (name "unconnected-(U5-DVDD-Pad8)") (class "Default")
      (node (ref "U5") (pin "8") (pinfunction "DVDD_8") (pintype "unspecified+no_connect"))
    )
    (net (code "121") (name "unconnected-(U5-SNSOUT-Pad10)") (class "Default")
      (node (ref "U5") (pin "10") (pinfunction "SNSOUT_10") (pintype "unspecified+no_connect"))
    )
    (net (code "122") (name "unconnected-(U5-SO-Pad11)") (class "Default")
      (node (ref "U5") (pin "11") (pinfunction "SO_11") (pintype "unspecified+no_connect"))
    )
    (net (code "123") (name "unconnected-(U5-nFAULT-Pad9)") (class "Default")
      (node (ref "U5") (pin "9") (pinfunction "nFAULT_9") (pintype "unspecified+no_connect"))
    )
    (net (code "124") (name "unconnected-(U8-CAN_RX_3{slash}CAN2_RX_3{slash}RXD2_2{slash}P4.6-Pad42)") (class "Default")
      (node (ref "U8") (pin "42") (pinfunction "CAN_RX_3/CAN2_RX_3/RXD2_2/P4.6_42") (pintype "unspecified+no_connect"))
    )
    (net (code "125") (name "unconnected-(U8-CAN_RX_3{slash}WR{slash}P4.2-Pad30)") (class "Default")
      (node (ref "U8") (pin "30") (pinfunction "CAN_RX_3/WR/P4.2_30") (pintype "unspecified+no_connect"))
    )
    (net (code "126") (name "unconnected-(U8-CAN_TX_3{slash}ALE{slash}P4.5-Pad41)") (class "Default")
      (node (ref "U8") (pin "41") (pinfunction "CAN_TX_3/ALE/P4.5_41") (pintype "unspecified+no_connect"))
    )
    (net (code "127") (name "unconnected-(U8-LIN_RX_2{slash}CAN2_RX_2{slash}RXD4_2{slash}P5.2-Pad48)") (class "Default")
      (node (ref "U8") (pin "48") (pinfunction "LIN_RX_2/CAN2_RX_2/RXD4_2/P5.2_48") (pintype "unspecified+no_connect"))
    )
    (net (code "128") (name "unconnected-(U8-LIN_RX{slash}CAN2_RX{slash}PWM7_3{slash}RXD4{slash}ADC10{slash}AD2{slash}P0.2-Pad45)") (class "Default")
      (node (ref "U8") (pin "45") (pinfunction "LIN_RX/CAN2_RX/PWM7_3/RXD4/ADC10/AD2/P0.2_45") (pintype "unspecified+no_connect"))
    )
    (net (code "129") (name "unconnected-(U8-P0.5{slash}AD5{slash}ADC13{slash}T3CLKO-Pad2)") (class "Default")
      (node (ref "U8") (pin "2") (pinfunction "P0.5/AD5/ADC13/T3CLKO_2") (pintype "unspecified+no_connect"))
    )
    (net (code "130") (name "unconnected-(U8-P0.6{slash}AD6{slash}ADC14{slash}T4{slash}PWMFLT2_2-Pad3)") (class "Default")
      (node (ref "U8") (pin "3") (pinfunction "P0.6/AD6/ADC14/T4/PWMFLT2_2_3") (pintype "unspecified+no_connect"))
    )
    (net (code "131") (name "unconnected-(U8-P0.7{slash}AD7{slash}T4CLKO-Pad4)") (class "Default")
      (node (ref "U8") (pin "4") (pinfunction "P0.7/AD7/T4CLKO_4") (pintype "unspecified+no_connect"))
    )
    (net (code "132") (name "unconnected-(U8-P1.0{slash}ADC0{slash}PWM1P{slash}RXD2-Pad5)") (class "Default")
      (node (ref "U8") (pin "5") (pinfunction "P1.0/ADC0/PWM1P/RXD2_5") (pintype "unspecified+no_connect"))
    )
    (net (code "133") (name "unconnected-(U8-P1.1{slash}ADC1{slash}PWM1N{slash}TXD2-Pad6)") (class "Default")
      (node (ref "U8") (pin "6") (pinfunction "P1.1/ADC1/PWM1N/TXD2_6") (pintype "unspecified+no_connect"))
    )
    (net (code "134") (name "unconnected-(U8-P1.3{slash}ADC3{slash}MOSI{slash}S2MOSI{slash}S1MOSI{slash}PWM2N{slash}T2CLKO-Pad12)") (class "Default")
      (node (ref "U8") (pin "12") (pinfunction "P1.3/ADC3/MOSI/S2MOSI/S1MOSI/PWM2N/T2CLKO_12") (pintype "unspecified+no_connect"))
    )
    (net (code "135") (name "unconnected-(U8-P1.4{slash}ADC4{slash}PWM3P{slash}MISO{slash}S1MISO{slash}S2MISO{slash}SDA-Pad8)") (class "Default")
      (node (ref "U8") (pin "8") (pinfunction "P1.4/ADC4/PWM3P/MISO/S1MISO/S2MISO/SDA_8") (pintype "unspecified+no_connect"))
    )
    (net (code "136") (name "unconnected-(U8-P1.5{slash}ADC5{slash}PWM3N{slash}SCLK{slash}S1CLK{slash}S2CLK{slash}SCL-Pad9)") (class "Default")
      (node (ref "U8") (pin "9") (pinfunction "P1.5/ADC5/PWM3N/SCLK/S1CLK/S2CLK/SCL_9") (pintype "unspecified+no_connect"))
    )
    (net (code "137") (name "unconnected-(U8-P1.6{slash}ADC6{slash}RXD_3{slash}PWM4P{slash}MCLKO_2{slash}XTALO-Pad10)") (class "Default")
      (node (ref "U8") (pin "10") (pinfunction "P1.6/ADC6/RXD_3/PWM4P/MCLKO_2/XTALO_10") (pintype "unspecified+no_connect"))
    )
    (net (code "138") (name "unconnected-(U8-P1.7{slash}ADC7{slash}TXD_3{slash}PWM4N{slash}PWM5_2{slash}XTALI-Pad11)") (class "Default")
      (node (ref "U8") (pin "11") (pinfunction "P1.7/ADC7/TXD_3/PWM4N/PWM5_2/XTALI_11") (pintype "unspecified+no_connect"))
    )
    (net (code "139") (name "unconnected-(U8-P3.2{slash}INT0{slash}SCLK_4{slash}SCL_4{slash}PWMETI{slash}PWMETI2-Pad21)") (class "Default")
      (node (ref "U8") (pin "21") (pinfunction "P3.2/INT0/SCLK_4/SCL_4/PWMETI/PWMETI2_21") (pintype "unspecified+no_connect"))
    )
    (net (code "140") (name "unconnected-(U8-P3.3{slash}INT1{slash}MISO_4{slash}SDA_4{slash}PWM4N_4{slash}PWM7_2-Pad22)") (class "Default")
      (node (ref "U8") (pin "22") (pinfunction "P3.3/INT1/MISO_4/SDA_4/PWM4N_4/PWM7_2_22") (pintype "unspecified+no_connect"))
    )
    (net (code "141") (name "unconnected-(U8-P3.4{slash}T0{slash}T1CLKO{slash}MOSI_4{slash}PWM4P_4{slash}PWM8_2{slash}CMPO-Pad23)") (class "Default")
      (node (ref "U8") (pin "23") (pinfunction "P3.4/T0/T1CLKO/MOSI_4/PWM4P_4/PWM8_2/CMPO_23") (pintype "unspecified+no_connect"))
    )
    (net (code "142") (name "unconnected-(U8-P4.0{slash}MOSI_3{slash}S1MOSI_3{slash}S2MOSI_3-Pad18)") (class "Default")
      (node (ref "U8") (pin "18") (pinfunction "P4.0/MOSI_3/S1MOSI_3/S2MOSI_3_18") (pintype "unspecified+no_connect"))
    )
    (net (code "143") (name "unconnected-(U8-P4.7{slash}TXD2_2{slash}CAN2_TX_3{slash}LIN_TX_3-Pad7)") (class "Default")
      (node (ref "U8") (pin "7") (pinfunction "P4.7/TXD2_2/CAN2_TX_3/LIN_TX_3_7") (pintype "unspecified+no_connect"))
    )
    (net (code "144") (name "unconnected-(U8-P5.3{slash}TXD4_2{slash}CAN2_TX_2{slash}LIN_TX_2-Pad1)") (class "Default")
      (node (ref "U8") (pin "1") (pinfunction "P5.3/TXD4_2/CAN2_TX_2/LIN_TX_2_1") (pintype "unspecified+no_connect"))
    )
    (net (code "145") (name "unconnected-(U8-P5.4{slash}ADC2{slash}PWM2P{slash}PWM6_2{slash}RST{slash}MCLKO{slash}SS_3{slash}S1SS_3{slash}S2SS_3{slash}T2-Pad14)") (class "Default")
      (node (ref "U8") (pin "14") (pinfunction "P5.4/ADC2/PWM2P/PWM6_2/RST/MCLKO/SS_3/S1SS_3/S2SS_3/T2_14") (pintype "unspecified+no_connect"))
    )
    (net (code "146") (name "unconnected-(U8-PWM4N_2{slash}A15{slash}P2.7-Pad40)") (class "Default")
      (node (ref "U8") (pin "40") (pinfunction "PWM4N_2/A15/P2.7_40") (pintype "unspecified+no_connect"))
    )
    (net (code "147") (name "unconnected-(U8-PWM4P_2{slash}A14{slash}P2.6-Pad39)") (class "Default")
      (node (ref "U8") (pin "39") (pinfunction "PWM4P_2/A14/P2.6_39") (pintype "unspecified+no_connect"))
    )
    (net (code "148") (name "unconnected-(U8-PWMETI_3{slash}CMPO_2{slash}S2MISO_3{slash}S1MISO_3{slash}MISO_3{slash}P4.1-Pad29)") (class "Default")
      (node (ref "U8") (pin "29") (pinfunction "PWMETI_3/CMPO_2/S2MISO_3/S1MISO_3/MISO_3/P4.1_29") (pintype "unspecified+no_connect"))
    )
    (net (code "149") (name "unconnected-(U8-PWMFLT{slash}SS_4{slash}T0CLKO{slash}T1{slash}P3.5-Pad26)") (class "Default")
      (node (ref "U8") (pin "26") (pinfunction "PWMFLT/SS_4/T0CLKO/T1/P3.5_26") (pintype "unspecified+no_connect"))
    )
    (net (code "150") (name "unconnected-(U8-S2SCLK_3{slash}S1SCLK_3{slash}SCLK{slash}RXD_4{slash}P4.3-Pad31)") (class "Default")
      (node (ref "U8") (pin "31") (pinfunction "S2SCLK_3/S1SCLK_3/SCLK/RXD_4/P4.3_31") (pintype "unspecified+no_connect"))
    )
    (net (code "151") (name "unconnected-(U8-T3{slash}ADC12{slash}AD4{slash}P0.4-Pad47)") (class "Default")
      (node (ref "U8") (pin "47") (pinfunction "T3/ADC12/AD4/P0.4_47") (pintype "unspecified+no_connect"))
    )
    (net (code "152") (name "unconnected-(U10-NC-Pad5)") (class "Default")
      (node (ref "U10") (pin "5") (pinfunction "NC_5") (pintype "unspecified+no_connect"))
    )
    (net (code "153") (name "unconnected-(U10-NC-Pad7)") (class "Default")
      (node (ref "U10") (pin "7") (pinfunction "NC_7") (pintype "unspecified+no_connect"))
    )
    (net (code "154") (name "unconnected-(U10-NC-Pad8)") (class "Default")
      (node (ref "U10") (pin "8") (pinfunction "NC_8") (pintype "unspecified+no_connect"))
    )
    (net (code "155") (name "unconnected-(U10-NC-Pad21)") (class "Default")
      (node (ref "U10") (pin "21") (pinfunction "NC_21") (pintype "unspecified+no_connect"))
    )
    (net (code "156") (name "unconnected-(U17-CAN_RX_3{slash}CAN2_RX_3{slash}RXD2_2{slash}P4.6-Pad42)") (class "Default")
      (node (ref "U17") (pin "42") (pinfunction "CAN_RX_3/CAN2_RX_3/RXD2_2/P4.6_42") (pintype "unspecified+no_connect"))
    )
    (net (code "157") (name "unconnected-(U17-CAN_RX_3{slash}WR{slash}P4.2-Pad30)") (class "Default")
      (node (ref "U17") (pin "30") (pinfunction "CAN_RX_3/WR/P4.2_30") (pintype "unspecified+no_connect"))
    )
    (net (code "158") (name "unconnected-(U17-CAN_TX_3{slash}ALE{slash}P4.5-Pad41)") (class "Default")
      (node (ref "U17") (pin "41") (pinfunction "CAN_TX_3/ALE/P4.5_41") (pintype "unspecified+no_connect"))
    )
    (net (code "159") (name "unconnected-(U17-LIN_RX_2{slash}CAN2_RX_2{slash}RXD4_2{slash}P5.2-Pad48)") (class "Default")
      (node (ref "U17") (pin "48") (pinfunction "LIN_RX_2/CAN2_RX_2/RXD4_2/P5.2_48") (pintype "unspecified+no_connect"))
    )
    (net (code "160") (name "unconnected-(U17-LIN_RX{slash}CAN2_RX{slash}PWM7_3{slash}RXD4{slash}ADC10{slash}AD2{slash}P0.2-Pad45)") (class "Default")
      (node (ref "U17") (pin "45") (pinfunction "LIN_RX/CAN2_RX/PWM7_3/RXD4/ADC10/AD2/P0.2_45") (pintype "unspecified+no_connect"))
    )
    (net (code "161") (name "unconnected-(U17-P0.5{slash}AD5{slash}ADC13{slash}T3CLKO-Pad2)") (class "Default")
      (node (ref "U17") (pin "2") (pinfunction "P0.5/AD5/ADC13/T3CLKO_2") (pintype "unspecified+no_connect"))
    )
    (net (code "162") (name "unconnected-(U17-P0.6{slash}AD6{slash}ADC14{slash}T4{slash}PWMFLT2_2-Pad3)") (class "Default")
      (node (ref "U17") (pin "3") (pinfunction "P0.6/AD6/ADC14/T4/PWMFLT2_2_3") (pintype "unspecified+no_connect"))
    )
    (net (code "163") (name "unconnected-(U17-P0.7{slash}AD7{slash}T4CLKO-Pad4)") (class "Default")
      (node (ref "U17") (pin "4") (pinfunction "P0.7/AD7/T4CLKO_4") (pintype "unspecified+no_connect"))
    )
    (net (code "164") (name "unconnected-(U17-P1.0{slash}ADC0{slash}PWM1P{slash}RXD2-Pad5)") (class "Default")
      (node (ref "U17") (pin "5") (pinfunction "P1.0/ADC0/PWM1P/RXD2_5") (pintype "unspecified+no_connect"))
    )
    (net (code "165") (name "unconnected-(U17-P1.1{slash}ADC1{slash}PWM1N{slash}TXD2-Pad6)") (class "Default")
      (node (ref "U17") (pin "6") (pinfunction "P1.1/ADC1/PWM1N/TXD2_6") (pintype "unspecified+no_connect"))
    )
    (net (code "166") (name "unconnected-(U17-P1.3{slash}ADC3{slash}MOSI{slash}S2MOSI{slash}S1MOSI{slash}PWM2N{slash}T2CLKO-Pad12)") (class "Default")
      (node (ref "U17") (pin "12") (pinfunction "P1.3/ADC3/MOSI/S2MOSI/S1MOSI/PWM2N/T2CLKO_12") (pintype "unspecified+no_connect"))
    )
    (net (code "167") (name "unconnected-(U17-P1.4{slash}ADC4{slash}PWM3P{slash}MISO{slash}S1MISO{slash}S2MISO{slash}SDA-Pad8)") (class "Default")
      (node (ref "U17") (pin "8") (pinfunction "P1.4/ADC4/PWM3P/MISO/S1MISO/S2MISO/SDA_8") (pintype "unspecified+no_connect"))
    )
    (net (code "168") (name "unconnected-(U17-P1.5{slash}ADC5{slash}PWM3N{slash}SCLK{slash}S1CLK{slash}S2CLK{slash}SCL-Pad9)") (class "Default")
      (node (ref "U17") (pin "9") (pinfunction "P1.5/ADC5/PWM3N/SCLK/S1CLK/S2CLK/SCL_9") (pintype "unspecified+no_connect"))
    )
    (net (code "169") (name "unconnected-(U17-P1.6{slash}ADC6{slash}RXD_3{slash}PWM4P{slash}MCLKO_2{slash}XTALO-Pad10)") (class "Default")
      (node (ref "U17") (pin "10") (pinfunction "P1.6/ADC6/RXD_3/PWM4P/MCLKO_2/XTALO_10") (pintype "unspecified+no_connect"))
    )
    (net (code "170") (name "unconnected-(U17-P1.7{slash}ADC7{slash}TXD_3{slash}PWM4N{slash}PWM5_2{slash}XTALI-Pad11)") (class "Default")
      (node (ref "U17") (pin "11") (pinfunction "P1.7/ADC7/TXD_3/PWM4N/PWM5_2/XTALI_11") (pintype "unspecified+no_connect"))
    )
    (net (code "171") (name "unconnected-(U17-P3.2{slash}INT0{slash}SCLK_4{slash}SCL_4{slash}PWMETI{slash}PWMETI2-Pad21)") (class "Default")
      (node (ref "U17") (pin "21") (pinfunction "P3.2/INT0/SCLK_4/SCL_4/PWMETI/PWMETI2_21") (pintype "unspecified+no_connect"))
    )
    (net (code "172") (name "unconnected-(U17-P3.3{slash}INT1{slash}MISO_4{slash}SDA_4{slash}PWM4N_4{slash}PWM7_2-Pad22)") (class "Default")
      (node (ref "U17") (pin "22") (pinfunction "P3.3/INT1/MISO_4/SDA_4/PWM4N_4/PWM7_2_22") (pintype "unspecified+no_connect"))
    )
    (net (code "173") (name "unconnected-(U17-P3.4{slash}T0{slash}T1CLKO{slash}MOSI_4{slash}PWM4P_4{slash}PWM8_2{slash}CMPO-Pad23)") (class "Default")
      (node (ref "U17") (pin "23") (pinfunction "P3.4/T0/T1CLKO/MOSI_4/PWM4P_4/PWM8_2/CMPO_23") (pintype "unspecified+no_connect"))
    )
    (net (code "174") (name "unconnected-(U17-P4.0{slash}MOSI_3{slash}S1MOSI_3{slash}S2MOSI_3-Pad18)") (class "Default")
      (node (ref "U17") (pin "18") (pinfunction "P4.0/MOSI_3/S1MOSI_3/S2MOSI_3_18") (pintype "unspecified+no_connect"))
    )
    (net (code "175") (name "unconnected-(U17-P4.7{slash}TXD2_2{slash}CAN2_TX_3{slash}LIN_TX_3-Pad7)") (class "Default")
      (node (ref "U17") (pin "7") (pinfunction "P4.7/TXD2_2/CAN2_TX_3/LIN_TX_3_7") (pintype "unspecified+no_connect"))
    )
    (net (code "176") (name "unconnected-(U17-P5.3{slash}TXD4_2{slash}CAN2_TX_2{slash}LIN_TX_2-Pad1)") (class "Default")
      (node (ref "U17") (pin "1") (pinfunction "P5.3/TXD4_2/CAN2_TX_2/LIN_TX_2_1") (pintype "unspecified+no_connect"))
    )
    (net (code "177") (name "unconnected-(U17-P5.4{slash}ADC2{slash}PWM2P{slash}PWM6_2{slash}RST{slash}MCLKO{slash}SS_3{slash}S1SS_3{slash}S2SS_3{slash}T2-Pad14)") (class "Default")
      (node (ref "U17") (pin "14") (pinfunction "P5.4/ADC2/PWM2P/PWM6_2/RST/MCLKO/SS_3/S1SS_3/S2SS_3/T2_14") (pintype "unspecified+no_connect"))
    )
    (net (code "178") (name "unconnected-(U17-PWM4N_2{slash}A15{slash}P2.7-Pad40)") (class "Default")
      (node (ref "U17") (pin "40") (pinfunction "PWM4N_2/A15/P2.7_40") (pintype "unspecified+no_connect"))
    )
    (net (code "179") (name "unconnected-(U17-PWM4P_2{slash}A14{slash}P2.6-Pad39)") (class "Default")
      (node (ref "U17") (pin "39") (pinfunction "PWM4P_2/A14/P2.6_39") (pintype "unspecified+no_connect"))
    )
    (net (code "180") (name "unconnected-(U17-PWMETI_3{slash}CMPO_2{slash}S2MISO_3{slash}S1MISO_3{slash}MISO_3{slash}P4.1-Pad29)") (class "Default")
      (node (ref "U17") (pin "29") (pinfunction "PWMETI_3/CMPO_2/S2MISO_3/S1MISO_3/MISO_3/P4.1_29") (pintype "unspecified+no_connect"))
    )
    (net (code "181") (name "unconnected-(U17-PWMFLT{slash}SS_4{slash}T0CLKO{slash}T1{slash}P3.5-Pad26)") (class "Default")
      (node (ref "U17") (pin "26") (pinfunction "PWMFLT/SS_4/T0CLKO/T1/P3.5_26") (pintype "unspecified+no_connect"))
    )
    (net (code "182") (name "unconnected-(U17-S2SCLK_3{slash}S1SCLK_3{slash}SCLK{slash}RXD_4{slash}P4.3-Pad31)") (class "Default")
      (node (ref "U17") (pin "31") (pinfunction "S2SCLK_3/S1SCLK_3/SCLK/RXD_4/P4.3_31") (pintype "unspecified+no_connect"))
    )
    (net (code "183") (name "unconnected-(U17-T3{slash}ADC12{slash}AD4{slash}P0.4-Pad47)") (class "Default")
      (node (ref "U17") (pin "47") (pinfunction "T3/ADC12/AD4/P0.4_47") (pintype "unspecified+no_connect"))
    )
    (net (code "184") (name "unconnected-(U19-NC-Pad5)") (class "Default")
      (node (ref "U19") (pin "5") (pinfunction "NC_5") (pintype "unspecified+no_connect"))
    )
    (net (code "185") (name "unconnected-(U19-NC-Pad7)") (class "Default")
      (node (ref "U19") (pin "7") (pinfunction "NC_7") (pintype "unspecified+no_connect"))
    )
    (net (code "186") (name "unconnected-(U19-NC-Pad8)") (class "Default")
      (node (ref "U19") (pin "8") (pinfunction "NC_8") (pintype "unspecified+no_connect"))
    )
    (net (code "187") (name "unconnected-(U19-NC-Pad21)") (class "Default")
      (node (ref "U19") (pin "21") (pinfunction "NC_21") (pintype "unspecified+no_connect"))
    )
  )
)
